# MSP-EXP430F5529LP.net
KiCad netlist of a schematic drawn in EAGLE
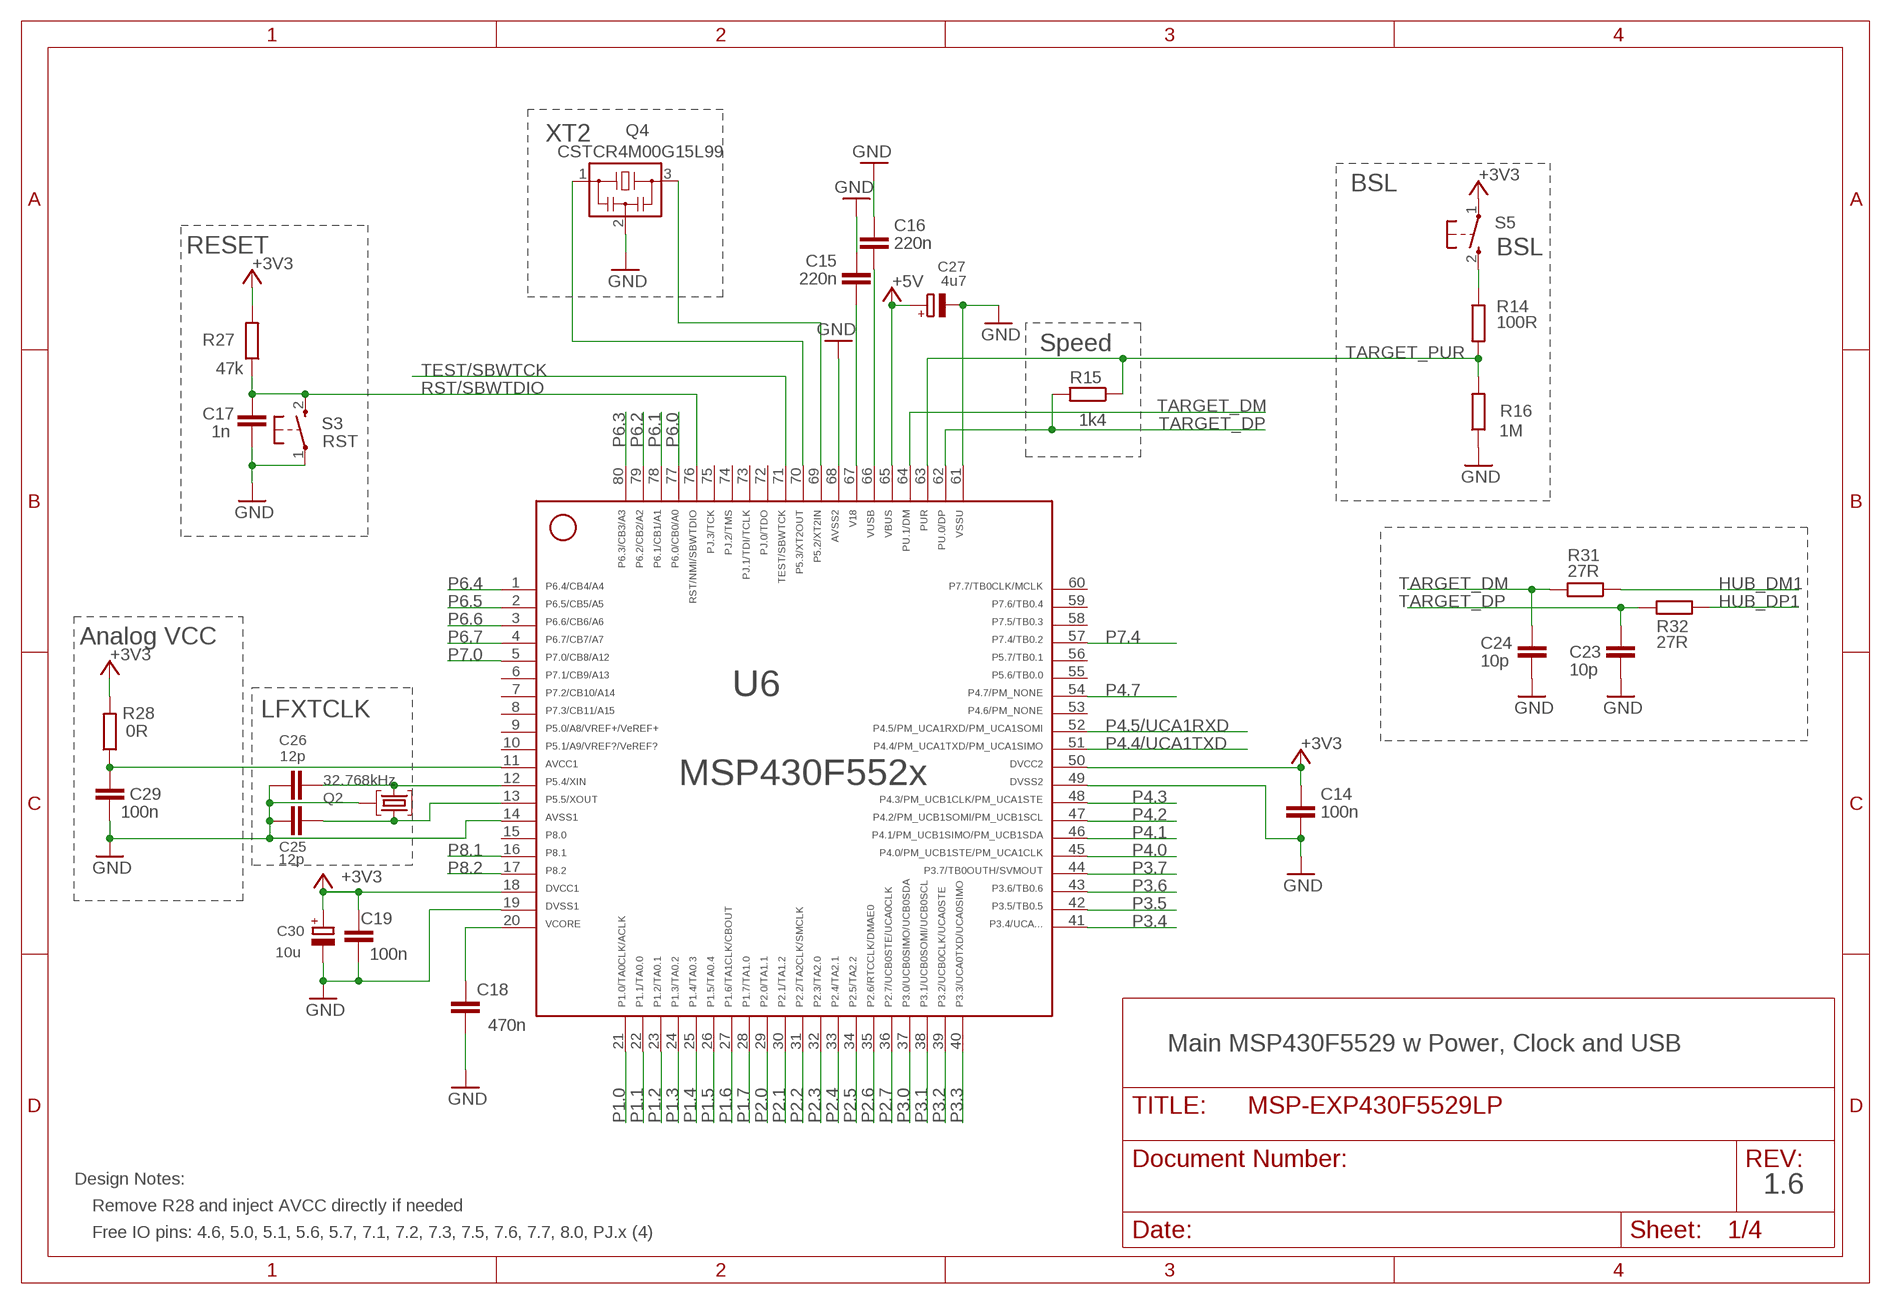
[diagram p0: schematic, sheet 1]
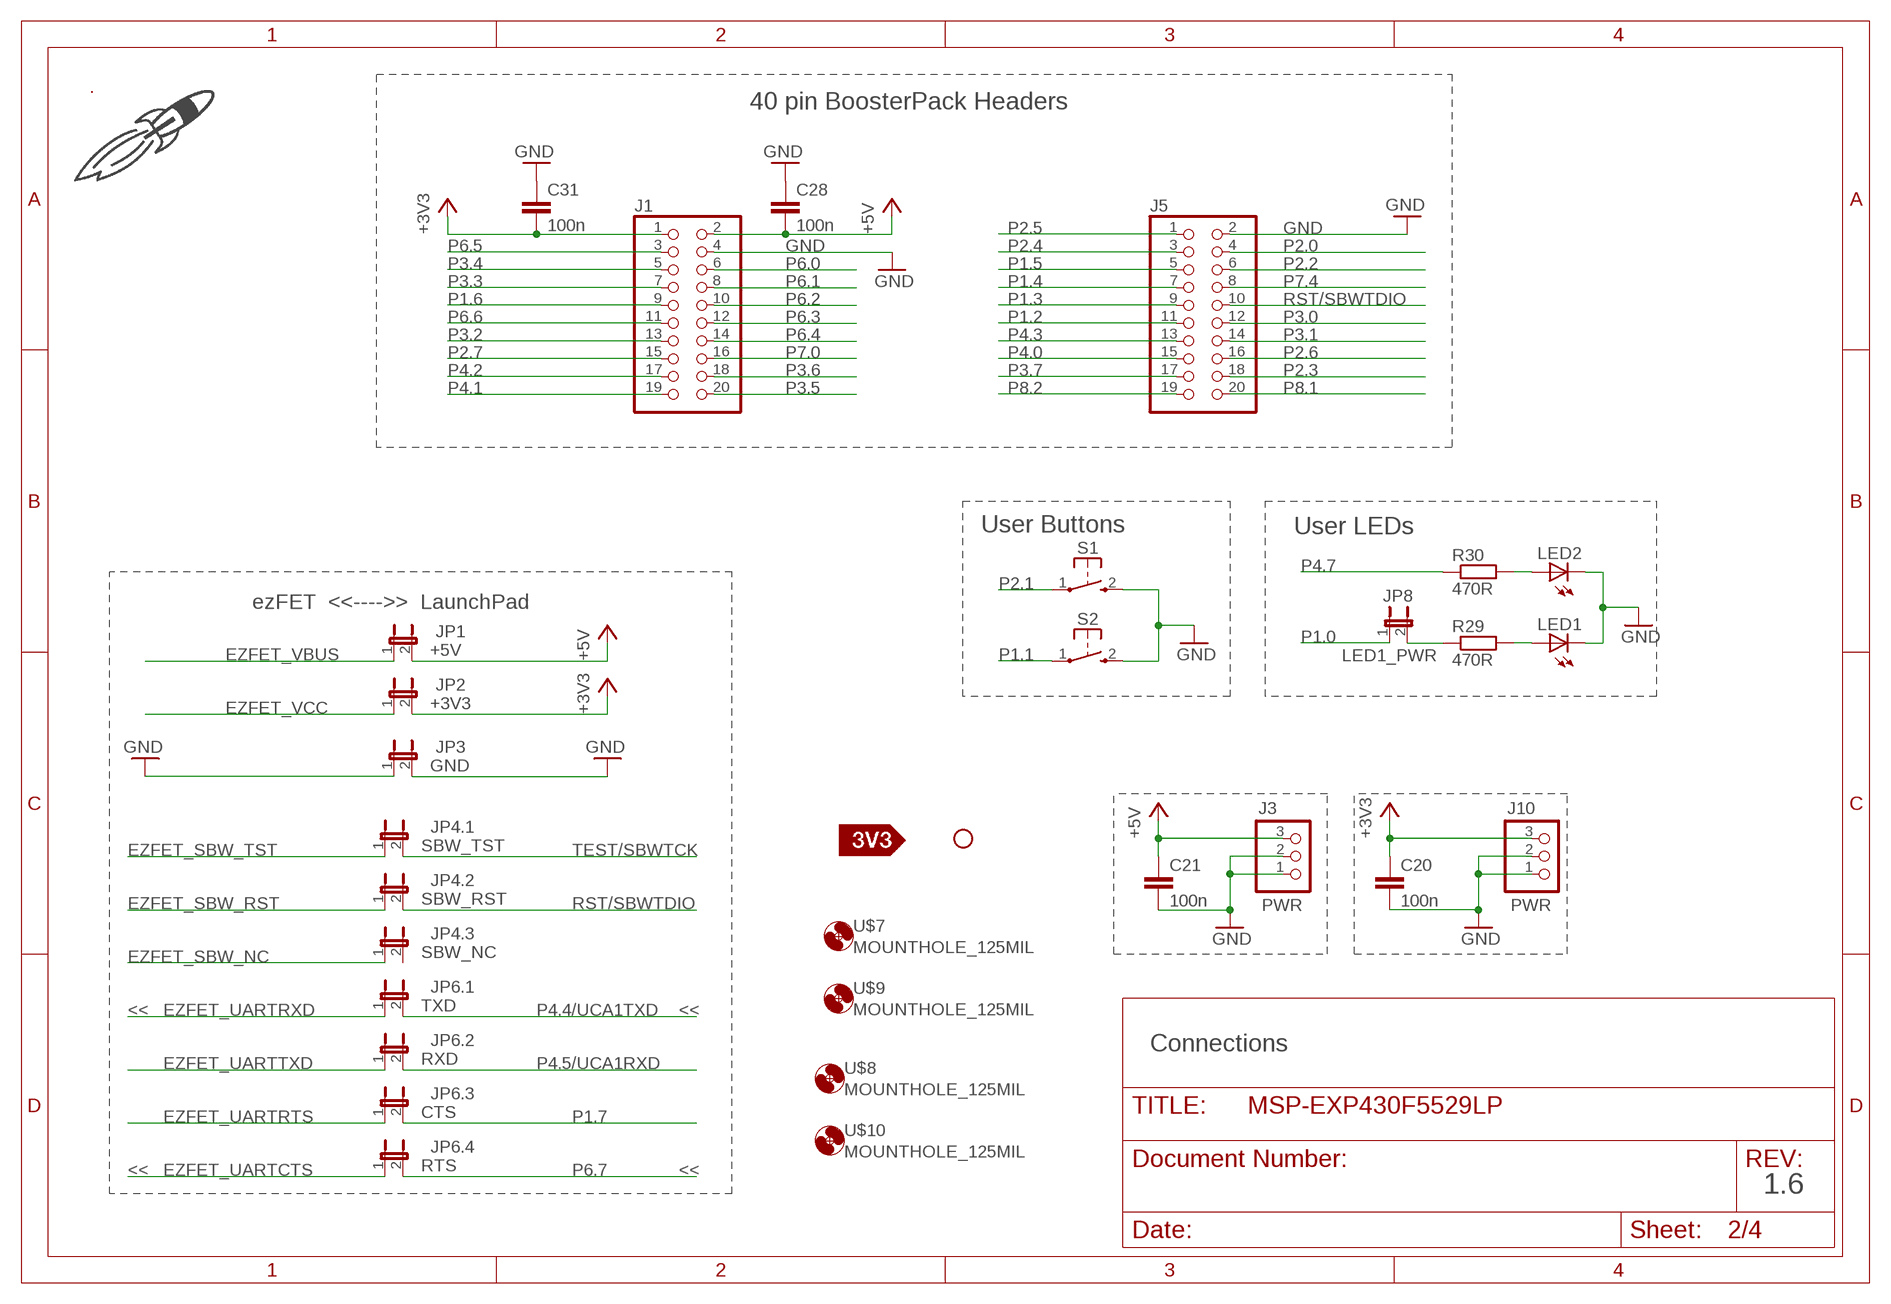
[diagram p1: schematic, sheet 2]
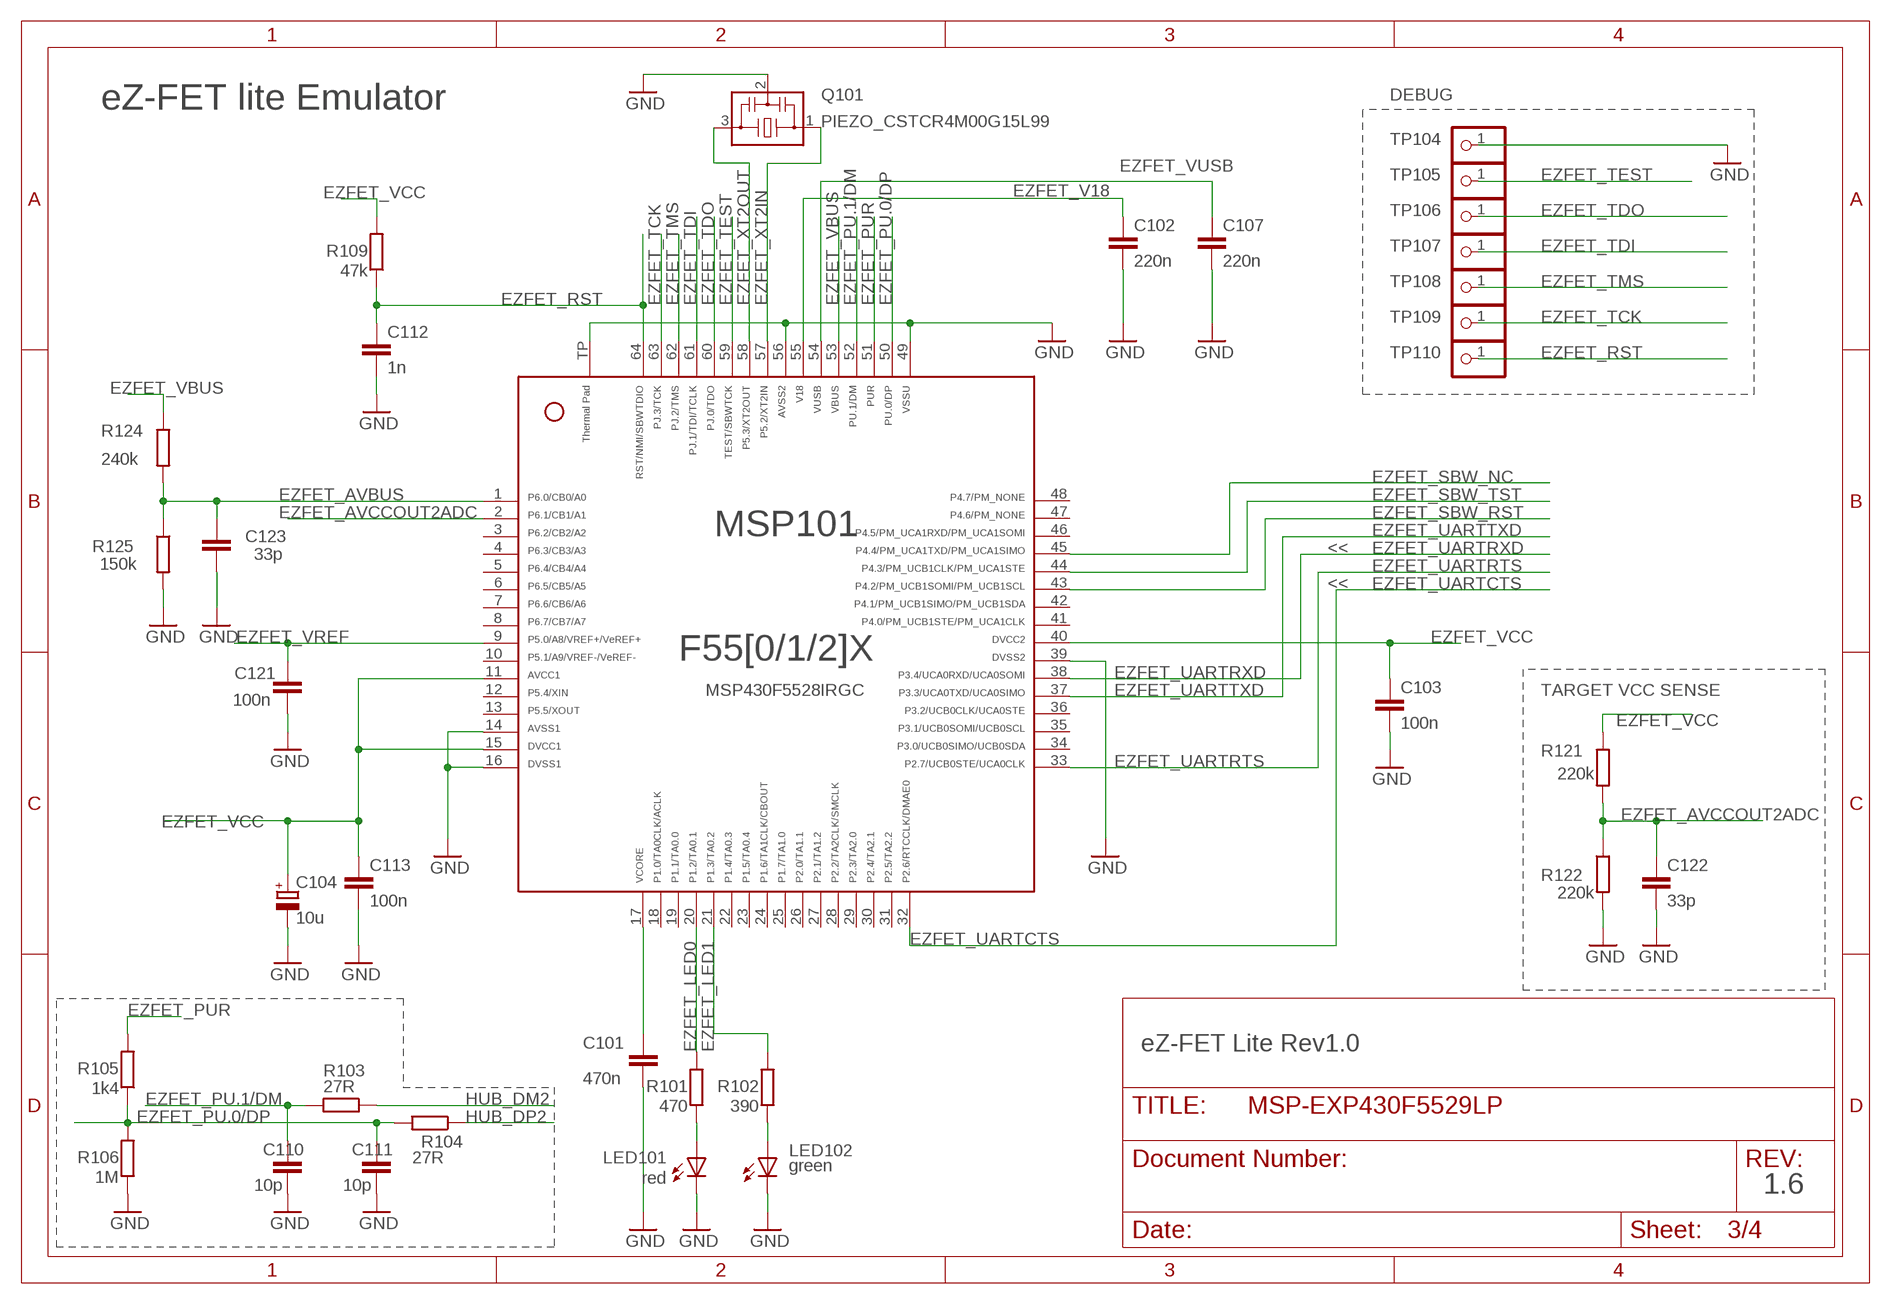
[diagram p2: schematic, sheet 3]
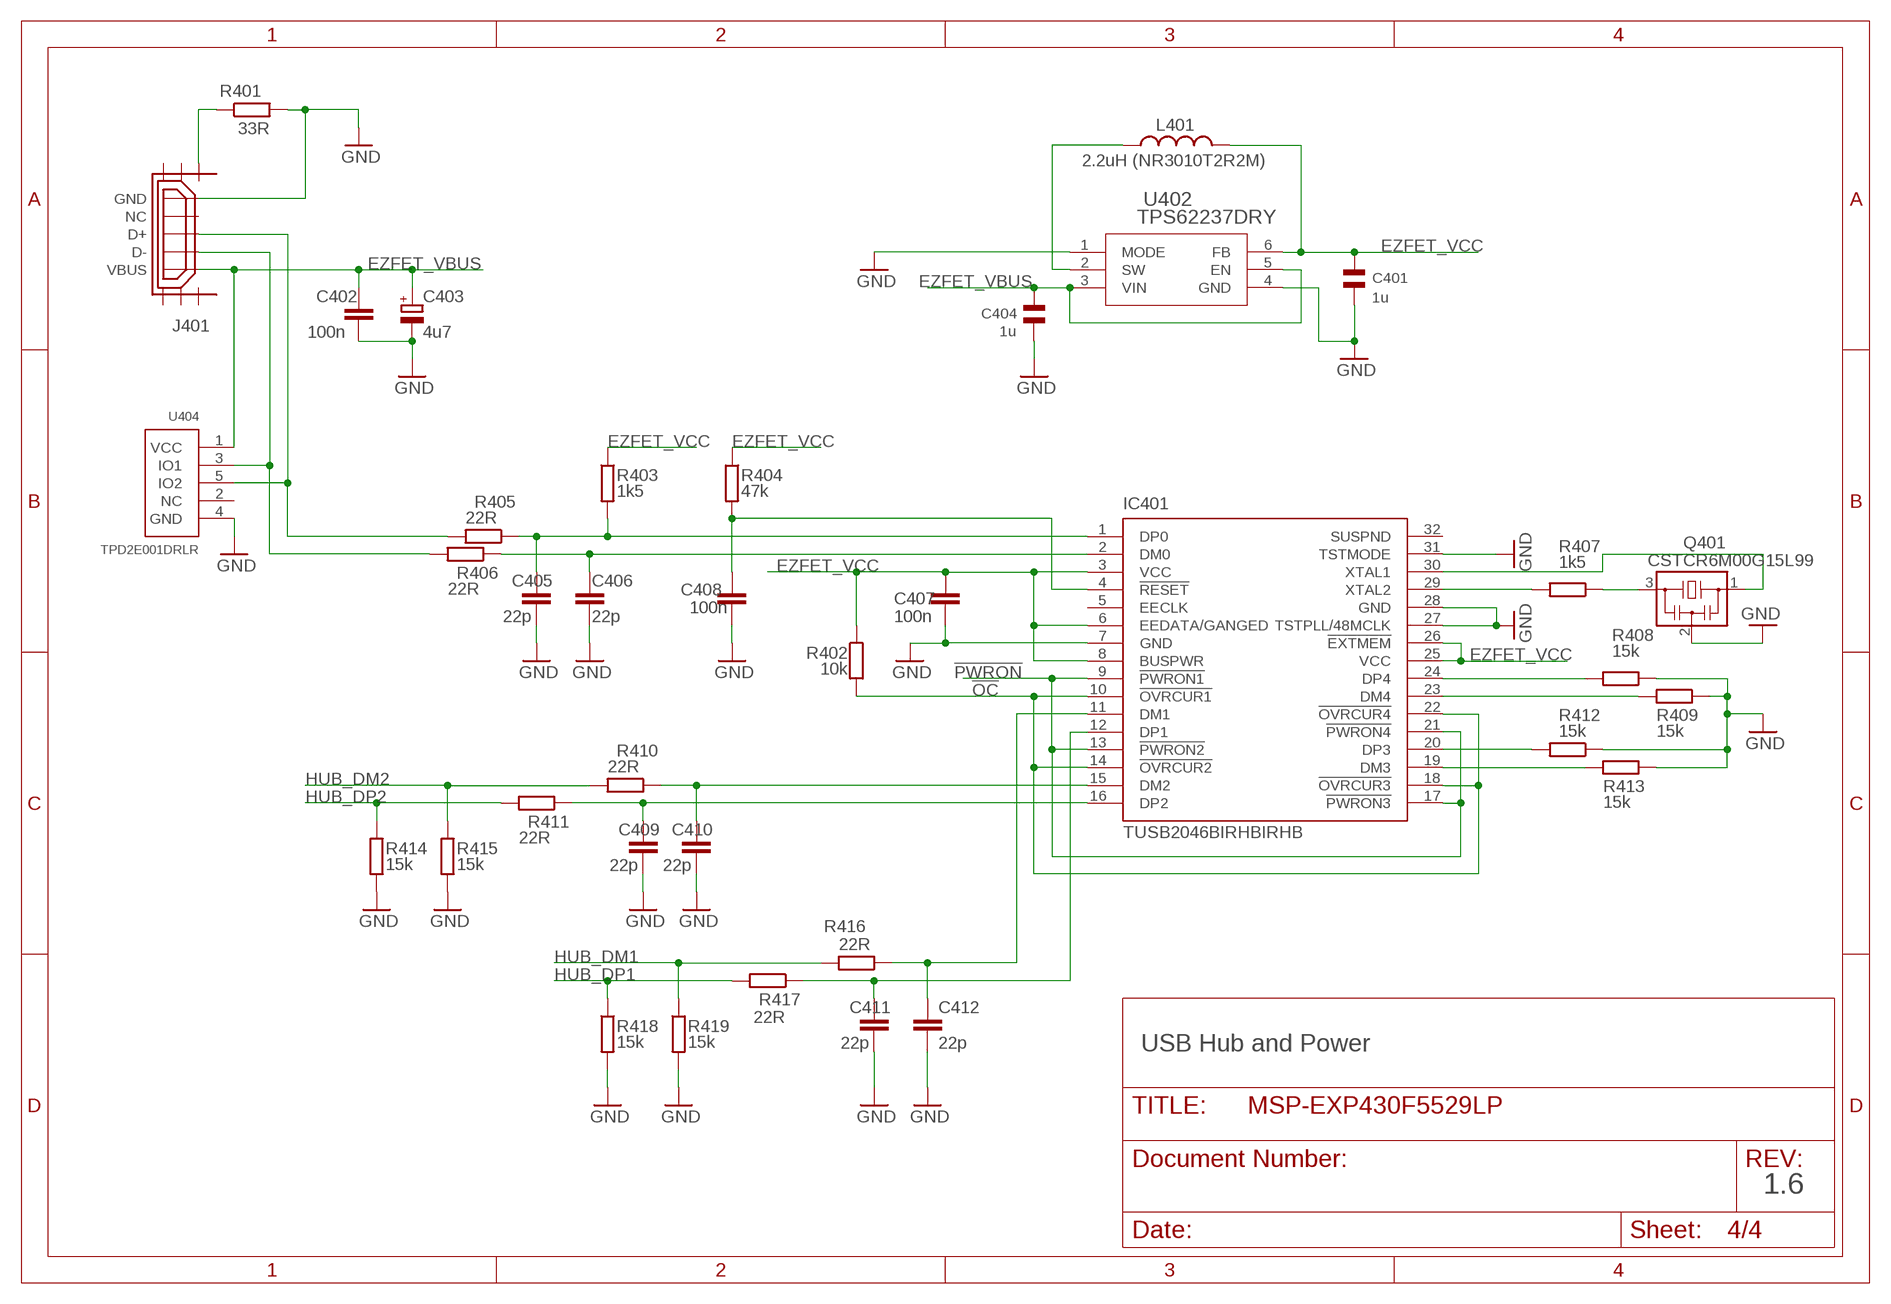
[diagram p3: schematic, sheet 4]

(export (version "E")
  (design (tool "Eeschema 10.0.6"))
  (components
    (comp (ref "C101")
      (value "470n")
      (footprint "eagle-import:0402")
      (libsource (lib "eagle-import") (part "C-EUCM0402"))
    )
    (comp (ref "C102")
      (value "220n")
      (footprint "eagle-import:0402")
      (libsource (lib "eagle-import") (part "C-EUCM0402"))
    )
    (comp (ref "C103")
      (value "100n")
      (footprint "eagle-import:0402")
      (libsource (lib "eagle-import") (part "C-EUCM0402"))
    )
    (comp (ref "C104")
      (value "10u")
      (footprint "eagle-import:A_3216-18R")
      (libsource (lib "eagle-import") (part "CPOL-EUA/3216-18R"))
    )
    (comp (ref "C107")
      (value "220n")
      (footprint "eagle-import:0402")
      (libsource (lib "eagle-import") (part "C-EUCM0402"))
    )
    (comp (ref "C110")
      (value "10p")
      (footprint "eagle-import:0402")
      (libsource (lib "eagle-import") (part "C-EUCM0402"))
    )
    (comp (ref "C111")
      (value "10p")
      (footprint "eagle-import:0402")
      (libsource (lib "eagle-import") (part "C-EUCM0402"))
    )
    (comp (ref "C112")
      (value "1n")
      (footprint "eagle-import:0402")
      (libsource (lib "eagle-import") (part "C-EUCM0402"))
    )
    (comp (ref "C113")
      (value "100n")
      (footprint "eagle-import:0402")
      (libsource (lib "eagle-import") (part "C-EUCM0402"))
    )
    (comp (ref "C121")
      (value "100n")
      (footprint "eagle-import:0402")
      (libsource (lib "eagle-import") (part "C-EUCM0402"))
    )
    (comp (ref "C122")
      (value "33p")
      (footprint "eagle-import:0402")
      (libsource (lib "eagle-import") (part "C-EUCM0402"))
    )
    (comp (ref "C123")
      (value "33p")
      (footprint "eagle-import:0402")
      (libsource (lib "eagle-import") (part "C-EUCM0402"))
    )
    (comp (ref "LED101")
      (value "red")
      (footprint "eagle-import:CHIP-LED0603")
      (libsource (lib "eagle-import") (part "LEDCHIP-LED0603"))
    )
    (comp (ref "LED102")
      (value "green")
      (footprint "eagle-import:CHIP-LED0603")
      (libsource (lib "eagle-import") (part "LEDCHIP-LED0603"))
    )
    (comp (ref "MSP101")
      (value "MSP430F5528IRGC")
      (footprint "eagle-import:RGC64")
      (libsource (lib "eagle-import") (part "F55[0/1/2]X---RGC64"))
    )
    (comp (ref "Q101")
      (value "PIEZO_CSTCR4M00G15L99")
      (footprint "eagle-import:MURATA-FILTER_CSTCR")
      (fields (field (name "MPN") "CSTCR6M00G53-R0"))
      (libsource (lib "eagle-import") (part "MURATA-FILTER_CSTCR6M00G53Z"))
    )
    (comp (ref "R101")
      (value "470")
      (footprint "eagle-import:0402")
      (libsource (lib "eagle-import") (part "R-EU_RM0402"))
    )
    (comp (ref "R102")
      (value "390")
      (footprint "eagle-import:0402")
      (libsource (lib "eagle-import") (part "R-EU_RM0402"))
    )
    (comp (ref "R103")
      (value "27R")
      (footprint "eagle-import:0402")
      (libsource (lib "eagle-import") (part "R-EU_RM0402"))
    )
    (comp (ref "R104")
      (value "27R")
      (footprint "eagle-import:0402")
      (libsource (lib "eagle-import") (part "R-EU_RM0402"))
    )
    (comp (ref "R105")
      (value "1k4")
      (footprint "eagle-import:0402")
      (libsource (lib "eagle-import") (part "R-EU_RM0402"))
    )
    (comp (ref "R106")
      (value "1M")
      (footprint "eagle-import:0402")
      (libsource (lib "eagle-import") (part "R-EU_RM0402"))
    )
    (comp (ref "R109")
      (value "47k")
      (footprint "eagle-import:0402")
      (libsource (lib "eagle-import") (part "R-EU_RM0402"))
    )
    (comp (ref "R121")
      (value "220k")
      (footprint "eagle-import:0402")
      (libsource (lib "eagle-import") (part "R-EU_RM0402"))
    )
    (comp (ref "R122")
      (value "220k")
      (footprint "eagle-import:0402")
      (libsource (lib "eagle-import") (part "R-EU_RM0402"))
    )
    (comp (ref "R124")
      (value "240k")
      (footprint "eagle-import:0402")
      (libsource (lib "eagle-import") (part "R-EU_RM0402"))
    )
    (comp (ref "R125")
      (value "150k")
      (footprint "eagle-import:0402")
      (libsource (lib "eagle-import") (part "R-EU_RM0402"))
    )
    (comp (ref "TP104")
      (value "TEST_PIN2")
      (footprint "eagle-import:1X01")
      (libsource (lib "eagle-import") (part "PINHD-1X1"))
    )
    (comp (ref "TP105")
      (value "TEST_PIN2")
      (footprint "eagle-import:1X01")
      (libsource (lib "eagle-import") (part "PINHD-1X1"))
    )
    (comp (ref "TP106")
      (value "TEST_PIN2")
      (footprint "eagle-import:1X01")
      (libsource (lib "eagle-import") (part "PINHD-1X1"))
    )
    (comp (ref "TP107")
      (value "TEST_PIN2")
      (footprint "eagle-import:1X01")
      (libsource (lib "eagle-import") (part "PINHD-1X1"))
    )
    (comp (ref "TP108")
      (value "TEST_PIN2")
      (footprint "eagle-import:1X01")
      (libsource (lib "eagle-import") (part "PINHD-1X1"))
    )
    (comp (ref "TP109")
      (value "TEST_PIN2")
      (footprint "eagle-import:1X01")
      (libsource (lib "eagle-import") (part "PINHD-1X1"))
    )
    (comp (ref "TP110")
      (value "TEST_PIN2")
      (footprint "eagle-import:1X01")
      (libsource (lib "eagle-import") (part "PINHD-1X1"))
    )
    (comp (ref "C20")
      (value "100n")
      (footprint "eagle-import:0402")
      (libsource (lib "eagle-import") (part "C-EUCM0402"))
    )
    (comp (ref "C21")
      (value "100n")
      (footprint "eagle-import:0402")
      (libsource (lib "eagle-import") (part "C-EUCM0402"))
    )
    (comp (ref "C28")
      (value "100n")
      (footprint "eagle-import:0402")
      (libsource (lib "eagle-import") (part "C-EUCM0402"))
    )
    (comp (ref "C31")
      (value "100n")
      (footprint "eagle-import:0402")
      (libsource (lib "eagle-import") (part "C-EUCM0402"))
    )
    (comp (ref "DRAW1")
      (value "LOGO-ROCKET-20X13MM-SCH-S")
      (footprint "eagle-import:LOGO-ROCKET-10X7MM-BRD")
      (libsource (lib "eagle-import") (part "LOGO-ROCKET-20X13MM-SCH-S"))
    )
    (comp (ref "J1")
      (value "PINHD-2X10")
      (footprint "eagle-import:2X10")
      (libsource (lib "eagle-import") (part "PINHD-2X10"))
    )
    (comp (ref "J3")
      (value "PWR")
      (footprint "eagle-import:1X03")
      (libsource (lib "eagle-import") (part "PINHD-1X3"))
    )
    (comp (ref "J5")
      (value "PINHD-2X10")
      (footprint "eagle-import:2X10")
      (libsource (lib "eagle-import") (part "PINHD-2X10"))
    )
    (comp (ref "J10")
      (value "PWR")
      (footprint "eagle-import:1X03")
      (libsource (lib "eagle-import") (part "PINHD-1X3"))
    )
    (comp (ref "JP1")
      (value "+5V")
      (footprint "eagle-import:JP1M")
      (libsource (lib "eagle-import") (part "JP1M"))
    )
    (comp (ref "JP2")
      (value "+3V3")
      (footprint "eagle-import:JP1M")
      (libsource (lib "eagle-import") (part "JP1M"))
    )
    (comp (ref "JP3")
      (value "GND")
      (footprint "eagle-import:JP1M")
      (libsource (lib "eagle-import") (part "JP1M"))
    )
    (comp (ref "JP4.1")
      (value "SBW_TST")
      (footprint "eagle-import:JP1M")
      (libsource (lib "eagle-import") (part "JP1M"))
    )
    (comp (ref "JP4.2")
      (value "SBW_RST")
      (footprint "eagle-import:JP1M")
      (libsource (lib "eagle-import") (part "JP1M"))
    )
    (comp (ref "JP4.3")
      (value "SBW_NC")
      (footprint "eagle-import:JP1M")
      (libsource (lib "eagle-import") (part "JP1M"))
    )
    (comp (ref "JP6.1")
      (value "TXD")
      (footprint "eagle-import:JP1M")
      (libsource (lib "eagle-import") (part "JP1M"))
    )
    (comp (ref "JP6.2")
      (value "RXD")
      (footprint "eagle-import:JP1M")
      (libsource (lib "eagle-import") (part "JP1M"))
    )
    (comp (ref "JP6.3")
      (value "CTS")
      (footprint "eagle-import:JP1M")
      (libsource (lib "eagle-import") (part "JP1M"))
    )
    (comp (ref "JP6.4")
      (value "RTS")
      (footprint "eagle-import:JP1M")
      (libsource (lib "eagle-import") (part "JP1M"))
    )
    (comp (ref "JP8")
      (value "LED1_PWR")
      (footprint "eagle-import:JP1")
      (libsource (lib "eagle-import") (part "JP1E"))
    )
    (comp (ref "LED1")
      (value "LEDCHIPLED_0603")
      (footprint "eagle-import:CHIPLED_0603")
      (libsource (lib "eagle-import") (part "LEDCHIPLED_0603"))
    )
    (comp (ref "LED2")
      (value "LEDCHIPLED_0603")
      (footprint "eagle-import:CHIPLED_0603")
      (libsource (lib "eagle-import") (part "LEDCHIPLED_0603"))
    )
    (comp (ref "R29")
      (value "470R")
      (footprint "eagle-import:0402")
      (libsource (lib "eagle-import") (part "R-EU_RM0402"))
    )
    (comp (ref "R30")
      (value "470R")
      (footprint "eagle-import:0402")
      (libsource (lib "eagle-import") (part "R-EU_RM0402"))
    )
    (comp (ref "S1")
      (value "PB")
      (footprint "eagle-import:PBTH")
      (libsource (lib "eagle-import") (part "PB"))
    )
    (comp (ref "S2")
      (value "PB")
      (footprint "eagle-import:PBTH")
      (libsource (lib "eagle-import") (part "PB"))
    )
    (comp (ref "U$4")
      (value "MS_TM")
      (footprint "eagle-import:MS_TM")
      (libsource (lib "eagle-import") (part "MS_TM"))
    )
    (comp (ref "U$6")
      (value "SILK_3V3_TAG")
      (footprint "eagle-import:SILK_3V3_TAG")
      (libsource (lib "eagle-import") (part "SILK_3V3_TAG"))
    )
    (comp (ref "U$7")
      (value "MOUNTHOLE_125MIL")
      (footprint "eagle-import:MOUNTHOLE_125MIL")
      (libsource (lib "eagle-import") (part "MOUNTHOLE_125MIL"))
    )
    (comp (ref "U$8")
      (value "MOUNTHOLE_125MIL")
      (footprint "eagle-import:MOUNTHOLE_125MIL")
      (libsource (lib "eagle-import") (part "MOUNTHOLE_125MIL"))
    )
    (comp (ref "U$9")
      (value "MOUNTHOLE_125MIL")
      (footprint "eagle-import:MOUNTHOLE_125MIL")
      (libsource (lib "eagle-import") (part "MOUNTHOLE_125MIL"))
    )
    (comp (ref "U$10")
      (value "MOUNTHOLE_125MIL")
      (footprint "eagle-import:MOUNTHOLE_125MIL")
      (libsource (lib "eagle-import") (part "MOUNTHOLE_125MIL"))
    )
    (comp (ref "U$11")
      (value "5529LP_REARSILK_REV1_6")
      (footprint "eagle-import:5529LP_REARSILK_REV1_6")
      (libsource (lib "eagle-import") (part "5529LP_REARSILK_REV1_6"))
    )
    (comp (ref "C14")
      (value "100n")
      (footprint "eagle-import:0402")
      (libsource (lib "eagle-import") (part "C-EUCM0402"))
    )
    (comp (ref "C15")
      (value "220n")
      (footprint "eagle-import:0402")
      (libsource (lib "eagle-import") (part "C-EUCM0402"))
    )
    (comp (ref "C16")
      (value "220n")
      (footprint "eagle-import:0402")
      (libsource (lib "eagle-import") (part "C-EUCM0402"))
    )
    (comp (ref "C17")
      (value "1n")
      (footprint "eagle-import:0402")
      (libsource (lib "eagle-import") (part "C-EUCM0402"))
    )
    (comp (ref "C18")
      (value "470n")
      (footprint "eagle-import:0402")
      (libsource (lib "eagle-import") (part "C-EUCM0402"))
    )
    (comp (ref "C19")
      (value "100n")
      (footprint "eagle-import:0402")
      (libsource (lib "eagle-import") (part "C-EUCM0402"))
    )
    (comp (ref "C23")
      (value "10p")
      (footprint "eagle-import:0402")
      (libsource (lib "eagle-import") (part "C-EUCM0402"))
    )
    (comp (ref "C24")
      (value "10p")
      (footprint "eagle-import:0402")
      (libsource (lib "eagle-import") (part "C-EUCM0402"))
    )
    (comp (ref "C25")
      (value "12p")
      (footprint "eagle-import:0402")
      (libsource (lib "eagle-import") (part "C-EUCM0402"))
    )
    (comp (ref "C26")
      (value "12p")
      (footprint "eagle-import:0402")
      (libsource (lib "eagle-import") (part "C-EUCM0402"))
    )
    (comp (ref "C27")
      (value "4u7")
      (footprint "eagle-import:A_3216-18R")
      (libsource (lib "eagle-import") (part "CPOL-EUA/3216-18R"))
    )
    (comp (ref "C29")
      (value "100n")
      (footprint "eagle-import:0402")
      (libsource (lib "eagle-import") (part "C-EUCM0402"))
    )
    (comp (ref "C30")
      (value "10u")
      (footprint "eagle-import:A_3216-18R")
      (libsource (lib "eagle-import") (part "CPOL-EUA/3216-18R"))
    )
    (comp (ref "Q2")
      (value "32.768kHz")
      (footprint "eagle-import:MS3V-T1R")
      (libsource (lib "eagle-import") (part "MS3V-T1R"))
    )
    (comp (ref "Q4")
      (value "CSTCR4M00G15L99")
      (footprint "eagle-import:MURATA-FILTER_CSTCR")
      (fields (field (name "MPN") "CSTCR6M00G53-R0"))
      (libsource (lib "eagle-import") (part "MURATA-FILTER_CSTCR6M00G53Z"))
    )
    (comp (ref "R14")
      (value "100R")
      (footprint "eagle-import:0402")
      (libsource (lib "eagle-import") (part "R-EU_RM0402"))
    )
    (comp (ref "R15")
      (value "1k4")
      (footprint "eagle-import:0402")
      (libsource (lib "eagle-import") (part "R-EU_RM0402"))
    )
    (comp (ref "R16")
      (value "1M")
      (footprint "eagle-import:0402")
      (libsource (lib "eagle-import") (part "R-EU_RM0402"))
    )
    (comp (ref "R27")
      (value "47k")
      (footprint "eagle-import:0402")
      (libsource (lib "eagle-import") (part "R-EU_RM0402"))
    )
    (comp (ref "R28")
      (value "0R")
      (footprint "eagle-import:0402")
      (libsource (lib "eagle-import") (part "R-EU_RM0402"))
    )
    (comp (ref "R31")
      (value "27R")
      (footprint "eagle-import:0402")
      (libsource (lib "eagle-import") (part "R-EU_RM0402"))
    )
    (comp (ref "R32")
      (value "27R")
      (footprint "eagle-import:0402")
      (libsource (lib "eagle-import") (part "R-EU_RM0402"))
    )
    (comp (ref "S3")
      (value "RST")
      (footprint "eagle-import:PBTH")
      (libsource (lib "eagle-import") (part "PB"))
    )
    (comp (ref "S5")
      (value "BSL")
      (footprint "eagle-import:PBTH")
      (libsource (lib "eagle-import") (part "PB"))
    )
    (comp (ref "U6")
      (value "MSP430F5529IPNR")
      (footprint "eagle-import:PN80")
      (libsource (lib "eagle-import") (part "F552X---PN80"))
    )
    (comp (ref "C401")
      (value "1u")
      (footprint "eagle-import:CSMD0805")
      (libsource (lib "eagle-import") (part "CSMD0805"))
    )
    (comp (ref "C402")
      (value "100n")
      (footprint "eagle-import:0402")
      (libsource (lib "eagle-import") (part "C-EUCM0402"))
    )
    (comp (ref "C403")
      (value "4u7")
      (footprint "eagle-import:A_3216-18R")
      (libsource (lib "eagle-import") (part "CPOL-EUA/3216-18R"))
    )
    (comp (ref "C404")
      (value "1u")
      (footprint "eagle-import:CSMD0805")
      (libsource (lib "eagle-import") (part "CSMD0805"))
    )
    (comp (ref "C405")
      (value "22p")
      (footprint "eagle-import:0402")
      (libsource (lib "eagle-import") (part "C-EUCM0402"))
    )
    (comp (ref "C406")
      (value "22p")
      (footprint "eagle-import:0402")
      (libsource (lib "eagle-import") (part "C-EUCM0402"))
    )
    (comp (ref "C407")
      (value "100n")
      (footprint "eagle-import:0402")
      (libsource (lib "eagle-import") (part "C-EUCM0402"))
    )
    (comp (ref "C408")
      (value "100n")
      (footprint "eagle-import:0402")
      (libsource (lib "eagle-import") (part "C-EUCM0402"))
    )
    (comp (ref "C409")
      (value "22p")
      (footprint "eagle-import:0402")
      (libsource (lib "eagle-import") (part "C-EUCM0402"))
    )
    (comp (ref "C410")
      (value "22p")
      (footprint "eagle-import:0402")
      (libsource (lib "eagle-import") (part "C-EUCM0402"))
    )
    (comp (ref "C411")
      (value "22p")
      (footprint "eagle-import:0402")
      (libsource (lib "eagle-import") (part "C-EUCM0402"))
    )
    (comp (ref "C412")
      (value "22p")
      (footprint "eagle-import:0402")
      (libsource (lib "eagle-import") (part "C-EUCM0402"))
    )
    (comp (ref "IC401")
      (value "TUSB2046BIRHBIRHB")
      (footprint "eagle-import:RHB_S-PQFP-N32")
      (fields (field (name "MPN") "TUSB2046BIRHBT"))
      (libsource (lib "eagle-import") (part "TUSB2046BIRHBIRHB"))
    )
    (comp (ref "J401")
      (value "USB_MICRO_FLIPPED")
      (footprint "eagle-import:HIROSE-ZX62R-B-5P")
      (libsource (lib "eagle-import") (part "USB_MICRO_FLIPPED"))
    )
    (comp (ref "L401")
      (value "2.2uH (NR3010T2R2M)")
      (footprint "eagle-import:L-NR3010")
      (libsource (lib "eagle-import") (part "L-NR3010"))
    )
    (comp (ref "Q401")
      (value "CSTCR6M00G15L99")
      (footprint "eagle-import:MURATA-FILTER_CSTCR")
      (fields (field (name "MPN") "CSTCR6M00G53-R0"))
      (libsource (lib "eagle-import") (part "MURATA-FILTER_CSTCR6M00G53Z"))
    )
    (comp (ref "R401")
      (value "33R")
      (footprint "eagle-import:0402")
      (libsource (lib "eagle-import") (part "R-EU_RM0402"))
    )
    (comp (ref "R402")
      (value "10k")
      (footprint "eagle-import:0402")
      (libsource (lib "eagle-import") (part "R-EU_RM0402"))
    )
    (comp (ref "R403")
      (value "1k5")
      (footprint "eagle-import:0402")
      (libsource (lib "eagle-import") (part "R-EU_RM0402"))
    )
    (comp (ref "R404")
      (value "47k")
      (footprint "eagle-import:0402")
      (libsource (lib "eagle-import") (part "R-EU_RM0402"))
    )
    (comp (ref "R405")
      (value "22R")
      (footprint "eagle-import:0402")
      (libsource (lib "eagle-import") (part "R-EU_RM0402"))
    )
    (comp (ref "R406")
      (value "22R")
      (footprint "eagle-import:0402")
      (libsource (lib "eagle-import") (part "R-EU_RM0402"))
    )
    (comp (ref "R407")
      (value "1k5")
      (footprint "eagle-import:0402")
      (libsource (lib "eagle-import") (part "R-EU_RM0402"))
    )
    (comp (ref "R408")
      (value "15k")
      (footprint "eagle-import:0402")
      (libsource (lib "eagle-import") (part "R-EU_RM0402"))
    )
    (comp (ref "R409")
      (value "15k")
      (footprint "eagle-import:0402")
      (libsource (lib "eagle-import") (part "R-EU_RM0402"))
    )
    (comp (ref "R410")
      (value "22R")
      (footprint "eagle-import:0402")
      (libsource (lib "eagle-import") (part "R-EU_RM0402"))
    )
    (comp (ref "R411")
      (value "22R")
      (footprint "eagle-import:0402")
      (libsource (lib "eagle-import") (part "R-EU_RM0402"))
    )
    (comp (ref "R412")
      (value "15k")
      (footprint "eagle-import:0402")
      (libsource (lib "eagle-import") (part "R-EU_RM0402"))
    )
    (comp (ref "R413")
      (value "15k")
      (footprint "eagle-import:0402")
      (libsource (lib "eagle-import") (part "R-EU_RM0402"))
    )
    (comp (ref "R414")
      (value "15k")
      (footprint "eagle-import:0402")
      (libsource (lib "eagle-import") (part "R-EU_RM0402"))
    )
    (comp (ref "R415")
      (value "15k")
      (footprint "eagle-import:0402")
      (libsource (lib "eagle-import") (part "R-EU_RM0402"))
    )
    (comp (ref "R416")
      (value "22R")
      (footprint "eagle-import:0402")
      (libsource (lib "eagle-import") (part "R-EU_RM0402"))
    )
    (comp (ref "R417")
      (value "22R")
      (footprint "eagle-import:0402")
      (libsource (lib "eagle-import") (part "R-EU_RM0402"))
    )
    (comp (ref "R418")
      (value "15k")
      (footprint "eagle-import:0402")
      (libsource (lib "eagle-import") (part "R-EU_RM0402"))
    )
    (comp (ref "R419")
      (value "15k")
      (footprint "eagle-import:0402")
      (libsource (lib "eagle-import") (part "R-EU_RM0402"))
    )
    (comp (ref "U402")
      (value "TPS62237DRY")
      (footprint "eagle-import:DRY6")
      (fields
        (field (name "GENERIC_PART_NUMBER") "TPS62231")
        (field (name "MANUFACTURER") "Texas Instruments")
        (field (name "MANUFACTURER_PART_NUMBER") "tps62231_dry_6")
      )
      (libsource (lib "eagle-import") (part "TPS6223X_DRY_6"))
    )
    (comp (ref "U404")
      (value "TPD2E001DRLR")
      (footprint "eagle-import:TPD2E001-DRL")
      (libsource (lib "eagle-import") (part "TPD2E001"))
    )
  )
  (nets
    (net (code "1") (name "+3V3") (class "Default")
      (node (ref "C14") (pin "1") (pinfunction "1_1") (pintype "passive"))
      (node (ref "C19") (pin "2") (pinfunction "2_2") (pintype "passive"))
      (node (ref "C20") (pin "1") (pinfunction "1_1") (pintype "passive"))
      (node (ref "C30") (pin "+") (pinfunction "+_+") (pintype "passive"))
      (node (ref "C31") (pin "2") (pinfunction "2_2") (pintype "passive"))
      (node (ref "J1") (pin "1") (pinfunction "1_1") (pintype "passive"))
      (node (ref "J10") (pin "3") (pinfunction "3_3") (pintype "passive"))
      (node (ref "JP2") (pin "2") (pinfunction "2_2") (pintype "passive"))
      (node (ref "R27") (pin "2") (pinfunction "2_2") (pintype "passive"))
      (node (ref "R28") (pin "2") (pinfunction "2_2") (pintype "passive"))
      (node (ref "S5") (pin "1") (pinfunction "P_1") (pintype "passive"))
      (node (ref "U6") (pin "18") (pinfunction "18_18") (pintype "power_in"))
      (node (ref "U6") (pin "50") (pinfunction "50_50") (pintype "power_in"))
    )
    (net (code "2") (name "+5V") (class "Default")
      (node (ref "C21") (pin "1") (pinfunction "1_1") (pintype "passive"))
      (node (ref "C27") (pin "+") (pinfunction "+_+") (pintype "passive"))
      (node (ref "C28") (pin "2") (pinfunction "2_2") (pintype "passive"))
      (node (ref "J1") (pin "2") (pinfunction "2_2") (pintype "passive"))
      (node (ref "J3") (pin "3") (pinfunction "3_3") (pintype "passive"))
      (node (ref "JP1") (pin "2") (pinfunction "2_2") (pintype "passive"))
      (node (ref "U6") (pin "65") (pinfunction "65_65") (pintype "power_in"))
    )
    (net (code "3") (name "EZFET_AVBUS") (class "Default")
      (node (ref "C123") (pin "2") (pinfunction "2_2") (pintype "passive"))
      (node (ref "MSP101") (pin "1") (pinfunction "1_1") (pintype "bidirectional"))
      (node (ref "R124") (pin "2") (pinfunction "2_2") (pintype "passive"))
      (node (ref "R125") (pin "1") (pinfunction "1_1") (pintype "passive"))
    )
    (net (code "4") (name "EZFET_AVCCOUT2ADC") (class "Default")
      (node (ref "C122") (pin "2") (pinfunction "2_2") (pintype "passive"))
      (node (ref "MSP101") (pin "2") (pinfunction "2_2") (pintype "bidirectional"))
      (node (ref "R121") (pin "2") (pinfunction "2_2") (pintype "passive"))
      (node (ref "R122") (pin "1") (pinfunction "1_1") (pintype "passive"))
    )
    (net (code "5") (name "EZFET_LED0") (class "Default")
      (node (ref "MSP101") (pin "20") (pinfunction "20_20") (pintype "bidirectional"))
      (node (ref "R101") (pin "2") (pinfunction "2_2") (pintype "passive"))
    )
    (net (code "6") (name "EZFET_LED1") (class "Default")
      (node (ref "MSP101") (pin "21") (pinfunction "21_21") (pintype "bidirectional"))
      (node (ref "R102") (pin "2") (pinfunction "2_2") (pintype "passive"))
    )
    (net (code "7") (name "EZFET_PU.0{slash}DP") (class "Default")
      (node (ref "C111") (pin "1") (pinfunction "1_1") (pintype "passive"))
      (node (ref "MSP101") (pin "50") (pinfunction "50_50") (pintype "bidirectional"))
      (node (ref "R104") (pin "2") (pinfunction "2_2") (pintype "passive"))
      (node (ref "R105") (pin "1") (pinfunction "1_1") (pintype "passive"))
      (node (ref "R106") (pin "2") (pinfunction "2_2") (pintype "passive"))
    )
    (net (code "8") (name "EZFET_PU.1{slash}DM") (class "Default")
      (node (ref "C110") (pin "1") (pinfunction "1_1") (pintype "passive"))
      (node (ref "MSP101") (pin "52") (pinfunction "52_52") (pintype "bidirectional"))
      (node (ref "R103") (pin "2") (pinfunction "2_2") (pintype "passive"))
    )
    (net (code "9") (name "EZFET_PUR") (class "Default")
      (node (ref "MSP101") (pin "51") (pinfunction "51_51") (pintype "bidirectional"))
      (node (ref "R105") (pin "2") (pinfunction "2_2") (pintype "passive"))
    )
    (net (code "10") (name "EZFET_RST") (class "Default")
      (node (ref "C112") (pin "1") (pinfunction "1_1") (pintype "passive"))
      (node (ref "MSP101") (pin "64") (pinfunction "64_64") (pintype "bidirectional"))
      (node (ref "R109") (pin "1") (pinfunction "1_1") (pintype "passive"))
      (node (ref "TP110") (pin "1") (pinfunction "1_1") (pintype "passive"))
    )
    (net (code "11") (name "EZFET_SBW_NC") (class "Default")
      (node (ref "JP4.3") (pin "1") (pinfunction "1_1") (pintype "passive"))
      (node (ref "MSP101") (pin "45") (pinfunction "45_45") (pintype "bidirectional"))
    )
    (net (code "12") (name "EZFET_SBW_RST") (class "Default")
      (node (ref "JP4.2") (pin "1") (pinfunction "1_1") (pintype "passive"))
      (node (ref "MSP101") (pin "43") (pinfunction "43_43") (pintype "bidirectional"))
    )
    (net (code "13") (name "EZFET_SBW_TST") (class "Default")
      (node (ref "JP4.1") (pin "1") (pinfunction "1_1") (pintype "passive"))
      (node (ref "MSP101") (pin "44") (pinfunction "44_44") (pintype "bidirectional"))
    )
    (net (code "14") (name "EZFET_TCK") (class "Default")
      (node (ref "MSP101") (pin "63") (pinfunction "63_63") (pintype "bidirectional"))
      (node (ref "TP109") (pin "1") (pinfunction "1_1") (pintype "passive"))
    )
    (net (code "15") (name "EZFET_TDI") (class "Default")
      (node (ref "MSP101") (pin "61") (pinfunction "61_61") (pintype "bidirectional"))
      (node (ref "TP107") (pin "1") (pinfunction "1_1") (pintype "passive"))
    )
    (net (code "16") (name "EZFET_TDO") (class "Default")
      (node (ref "MSP101") (pin "60") (pinfunction "60_60") (pintype "bidirectional"))
      (node (ref "TP106") (pin "1") (pinfunction "1_1") (pintype "passive"))
    )
    (net (code "17") (name "EZFET_TEST") (class "Default")
      (node (ref "MSP101") (pin "59") (pinfunction "59_59") (pintype "input"))
      (node (ref "TP105") (pin "1") (pinfunction "1_1") (pintype "passive"))
    )
    (net (code "18") (name "EZFET_TMS") (class "Default")
      (node (ref "MSP101") (pin "62") (pinfunction "62_62") (pintype "bidirectional"))
      (node (ref "TP108") (pin "1") (pinfunction "1_1") (pintype "passive"))
    )
    (net (code "19") (name "EZFET_UARTCTS") (class "Default")
      (node (ref "JP6.4") (pin "1") (pinfunction "1_1") (pintype "passive"))
      (node (ref "MSP101") (pin "32") (pinfunction "32_32") (pintype "bidirectional"))
    )
    (net (code "20") (name "EZFET_UARTRTS") (class "Default")
      (node (ref "JP6.3") (pin "1") (pinfunction "1_1") (pintype "passive"))
      (node (ref "MSP101") (pin "33") (pinfunction "33_33") (pintype "bidirectional"))
    )
    (net (code "21") (name "EZFET_UARTRXD") (class "Default")
      (node (ref "JP6.1") (pin "1") (pinfunction "1_1") (pintype "passive"))
      (node (ref "MSP101") (pin "38") (pinfunction "38_38") (pintype "bidirectional"))
    )
    (net (code "22") (name "EZFET_UARTTXD") (class "Default")
      (node (ref "JP6.2") (pin "1") (pinfunction "1_1") (pintype "passive"))
      (node (ref "MSP101") (pin "37") (pinfunction "37_37") (pintype "bidirectional"))
    )
    (net (code "23") (name "EZFET_V18") (class "Default")
      (node (ref "C102") (pin "1") (pinfunction "1_1") (pintype "passive"))
      (node (ref "MSP101") (pin "55") (pinfunction "55_55") (pintype "power_in"))
    )
    (net (code "24") (name "EZFET_VBUS") (class "Default")
      (node (ref "C402") (pin "1") (pinfunction "1_1") (pintype "passive"))
      (node (ref "C403") (pin "+") (pinfunction "+_+") (pintype "passive"))
      (node (ref "C404") (pin "2") (pinfunction "2_2") (pintype "passive"))
      (node (ref "J401") (pin "VBUS") (pinfunction "VBUS_VBUS") (pintype "input"))
      (node (ref "JP1") (pin "1") (pinfunction "1_1") (pintype "passive"))
      (node (ref "MSP101") (pin "53") (pinfunction "53_53") (pintype "power_in"))
      (node (ref "R124") (pin "1") (pinfunction "1_1") (pintype "passive"))
      (node (ref "U402") (pin "3") (pinfunction "VIN_3") (pintype "power_in"))
      (node (ref "U402") (pin "5") (pinfunction "EN_5") (pintype "input"))
      (node (ref "U404") (pin "1") (pinfunction "VCC_1") (pintype "power_in"))
    )
    (net (code "25") (name "EZFET_VCC") (class "Default")
      (node (ref "C103") (pin "1") (pinfunction "1_1") (pintype "passive"))
      (node (ref "C104") (pin "+") (pinfunction "+_+") (pintype "passive"))
      (node (ref "C113") (pin "1") (pinfunction "1_1") (pintype "passive"))
      (node (ref "C401") (pin "2") (pinfunction "2_2") (pintype "passive"))
      (node (ref "C407") (pin "1") (pinfunction "1_1") (pintype "passive"))
      (node (ref "IC401") (pin "25") (pinfunction "VCC_25") (pintype "power_in"))
      (node (ref "IC401") (pin "26") (pinfunction "~{EXTMEM}_26") (pintype "input"))
      (node (ref "IC401") (pin "3") (pinfunction "VCC_3") (pintype "power_in"))
      (node (ref "IC401") (pin "6") (pinfunction "EEDATA/GANGED_6") (pintype "bidirectional"))
      (node (ref "IC401") (pin "8") (pinfunction "BUSPWR_8") (pintype "input"))
      (node (ref "JP2") (pin "1") (pinfunction "1_1") (pintype "passive"))
      (node (ref "L401") (pin "P$2") (pinfunction "2_P$2") (pintype "passive"))
      (node (ref "MSP101") (pin "11") (pinfunction "11_11") (pintype "power_in"))
      (node (ref "MSP101") (pin "15") (pinfunction "15_15") (pintype "power_in"))
      (node (ref "MSP101") (pin "40") (pinfunction "40_40") (pintype "power_in"))
      (node (ref "R109") (pin "2") (pinfunction "2_2") (pintype "passive"))
      (node (ref "R121") (pin "1") (pinfunction "1_1") (pintype "passive"))
      (node (ref "R402") (pin "1") (pinfunction "1_1") (pintype "passive"))
      (node (ref "R403") (pin "1") (pinfunction "1_1") (pintype "passive"))
      (node (ref "R404") (pin "1") (pinfunction "1_1") (pintype "passive"))
      (node (ref "U402") (pin "6") (pinfunction "FB_6") (pintype "input"))
    )
    (net (code "26") (name "EZFET_VREF") (class "Default")
      (node (ref "C121") (pin "1") (pinfunction "1_1") (pintype "passive"))
      (node (ref "MSP101") (pin "9") (pinfunction "9_9") (pintype "bidirectional"))
    )
    (net (code "27") (name "EZFET_VUSB") (class "Default")
      (node (ref "C107") (pin "1") (pinfunction "1_1") (pintype "passive"))
      (node (ref "MSP101") (pin "54") (pinfunction "54_54") (pintype "power_in"))
    )
    (net (code "28") (name "EZFET_XT2IN") (class "Default")
      (node (ref "MSP101") (pin "57") (pinfunction "57_57") (pintype "bidirectional"))
      (node (ref "Q101") (pin "1") (pinfunction "1_1") (pintype "passive"))
    )
    (net (code "29") (name "EZFET_XT2OUT") (class "Default")
      (node (ref "MSP101") (pin "58") (pinfunction "58_58") (pintype "bidirectional"))
      (node (ref "Q101") (pin "3") (pinfunction "3_3") (pintype "passive"))
    )
    (net (code "30") (name "GND") (class "Default")
      (node (ref "C101") (pin "2") (pinfunction "2_2") (pintype "passive"))
      (node (ref "C102") (pin "2") (pinfunction "2_2") (pintype "passive"))
      (node (ref "C103") (pin "2") (pinfunction "2_2") (pintype "passive"))
      (node (ref "C104") (pin "-") (pinfunction "-_-") (pintype "passive"))
      (node (ref "C107") (pin "2") (pinfunction "2_2") (pintype "passive"))
      (node (ref "C110") (pin "2") (pinfunction "2_2") (pintype "passive"))
      (node (ref "C111") (pin "2") (pinfunction "2_2") (pintype "passive"))
      (node (ref "C112") (pin "2") (pinfunction "2_2") (pintype "passive"))
      (node (ref "C113") (pin "2") (pinfunction "2_2") (pintype "passive"))
      (node (ref "C121") (pin "2") (pinfunction "2_2") (pintype "passive"))
      (node (ref "C122") (pin "1") (pinfunction "1_1") (pintype "passive"))
      (node (ref "C123") (pin "1") (pinfunction "1_1") (pintype "passive"))
      (node (ref "C14") (pin "2") (pinfunction "2_2") (pintype "passive"))
      (node (ref "C15") (pin "2") (pinfunction "2_2") (pintype "passive"))
      (node (ref "C16") (pin "2") (pinfunction "2_2") (pintype "passive"))
      (node (ref "C17") (pin "2") (pinfunction "2_2") (pintype "passive"))
      (node (ref "C18") (pin "1") (pinfunction "1_1") (pintype "passive"))
      (node (ref "C19") (pin "1") (pinfunction "1_1") (pintype "passive"))
      (node (ref "C20") (pin "2") (pinfunction "2_2") (pintype "passive"))
      (node (ref "C21") (pin "2") (pinfunction "2_2") (pintype "passive"))
      (node (ref "C23") (pin "2") (pinfunction "2_2") (pintype "passive"))
      (node (ref "C24") (pin "2") (pinfunction "2_2") (pintype "passive"))
      (node (ref "C25") (pin "1") (pinfunction "1_1") (pintype "passive"))
      (node (ref "C26") (pin "1") (pinfunction "1_1") (pintype "passive"))
      (node (ref "C27") (pin "-") (pinfunction "-_-") (pintype "passive"))
      (node (ref "C28") (pin "1") (pinfunction "1_1") (pintype "passive"))
      (node (ref "C29") (pin "2") (pinfunction "2_2") (pintype "passive"))
      (node (ref "C30") (pin "-") (pinfunction "-_-") (pintype "passive"))
      (node (ref "C31") (pin "1") (pinfunction "1_1") (pintype "passive"))
      (node (ref "C401") (pin "1") (pinfunction "1_1") (pintype "passive"))
      (node (ref "C402") (pin "2") (pinfunction "2_2") (pintype "passive"))
      (node (ref "C403") (pin "-") (pinfunction "-_-") (pintype "passive"))
      (node (ref "C404") (pin "1") (pinfunction "1_1") (pintype "passive"))
      (node (ref "C405") (pin "2") (pinfunction "2_2") (pintype "passive"))
      (node (ref "C406") (pin "2") (pinfunction "2_2") (pintype "passive"))
      (node (ref "C407") (pin "2") (pinfunction "2_2") (pintype "passive"))
      (node (ref "C408") (pin "2") (pinfunction "2_2") (pintype "passive"))
      (node (ref "C409") (pin "2") (pinfunction "2_2") (pintype "passive"))
      (node (ref "C410") (pin "2") (pinfunction "2_2") (pintype "passive"))
      (node (ref "C411") (pin "2") (pinfunction "2_2") (pintype "passive"))
      (node (ref "C412") (pin "2") (pinfunction "2_2") (pintype "passive"))
      (node (ref "IC401") (pin "27") (pinfunction "TSTPLL/48MCLK_27") (pintype "bidirectional"))
      (node (ref "IC401") (pin "28") (pinfunction "GND_28") (pintype "power_in"))
      (node (ref "IC401") (pin "31") (pinfunction "TSTMODE_31") (pintype "input"))
      (node (ref "IC401") (pin "7") (pinfunction "GND_7") (pintype "power_in"))
      (node (ref "J1") (pin "4") (pinfunction "4_4") (pintype "passive"))
      (node (ref "J10") (pin "1") (pinfunction "1_1") (pintype "passive"))
      (node (ref "J10") (pin "2") (pinfunction "2_2") (pintype "passive"))
      (node (ref "J3") (pin "1") (pinfunction "1_1") (pintype "passive"))
      (node (ref "J3") (pin "2") (pinfunction "2_2") (pintype "passive"))
      (node (ref "J401") (pin "GND") (pinfunction "GND_GND") (pintype "input"))
      (node (ref "J5") (pin "2") (pinfunction "2_2") (pintype "passive"))
      (node (ref "JP3") (pin "1") (pinfunction "1_1") (pintype "passive"))
      (node (ref "JP3") (pin "2") (pinfunction "2_2") (pintype "passive"))
      (node (ref "LED1") (pin "C") (pinfunction "C_C") (pintype "passive"))
      (node (ref "LED101") (pin "C") (pinfunction "C_C") (pintype "passive"))
      (node (ref "LED102") (pin "C") (pinfunction "C_C") (pintype "passive"))
      (node (ref "LED2") (pin "C") (pinfunction "C_C") (pintype "passive"))
      (node (ref "MSP101") (pin "14") (pinfunction "14_14") (pintype "power_in"))
      (node (ref "MSP101") (pin "16") (pinfunction "16_16") (pintype "power_in"))
      (node (ref "MSP101") (pin "39") (pinfunction "39_39") (pintype "power_in"))
      (node (ref "MSP101") (pin "49") (pinfunction "49_49") (pintype "power_in"))
      (node (ref "MSP101") (pin "56") (pinfunction "56_56") (pintype "power_in"))
      (node (ref "MSP101") (pin "TP") (pinfunction "TP_TP") (pintype "power_in"))
      (node (ref "Q101") (pin "2") (pinfunction "2_2") (pintype "passive"))
      (node (ref "Q2") (pin "P3") (pinfunction "GND_P3") (pintype "power_in"))
      (node (ref "Q4") (pin "2") (pinfunction "2_2") (pintype "passive"))
      (node (ref "Q401") (pin "2") (pinfunction "2_2") (pintype "passive"))
      (node (ref "R106") (pin "1") (pinfunction "1_1") (pintype "passive"))
      (node (ref "R122") (pin "2") (pinfunction "2_2") (pintype "passive"))
      (node (ref "R125") (pin "2") (pinfunction "2_2") (pintype "passive"))
      (node (ref "R16") (pin "1") (pinfunction "1_1") (pintype "passive"))
      (node (ref "R401") (pin "2") (pinfunction "2_2") (pintype "passive"))
      (node (ref "R408") (pin "1") (pinfunction "1_1") (pintype "passive"))
      (node (ref "R409") (pin "1") (pinfunction "1_1") (pintype "passive"))
      (node (ref "R412") (pin "1") (pinfunction "1_1") (pintype "passive"))
      (node (ref "R413") (pin "1") (pinfunction "1_1") (pintype "passive"))
      (node (ref "R414") (pin "2") (pinfunction "2_2") (pintype "passive"))
      (node (ref "R415") (pin "2") (pinfunction "2_2") (pintype "passive"))
      (node (ref "R418") (pin "2") (pinfunction "2_2") (pintype "passive"))
      (node (ref "R419") (pin "2") (pinfunction "2_2") (pintype "passive"))
      (node (ref "S1") (pin "2") (pinfunction "S_2") (pintype "passive"))
      (node (ref "S2") (pin "2") (pinfunction "S_2") (pintype "passive"))
      (node (ref "S3") (pin "1") (pinfunction "P_1") (pintype "passive"))
      (node (ref "TP104") (pin "1") (pinfunction "1_1") (pintype "passive"))
      (node (ref "U402") (pin "1") (pinfunction "MODE_1") (pintype "input"))
      (node (ref "U402") (pin "4") (pinfunction "GND_4") (pintype "power_in"))
      (node (ref "U404") (pin "4") (pinfunction "GND_4") (pintype "power_in"))
      (node (ref "U6") (pin "14") (pinfunction "14_14") (pintype "power_in"))
      (node (ref "U6") (pin "19") (pinfunction "19_19") (pintype "power_in"))
      (node (ref "U6") (pin "49") (pinfunction "49_49") (pintype "power_in"))
      (node (ref "U6") (pin "61") (pinfunction "61_61") (pintype "power_in"))
      (node (ref "U6") (pin "68") (pinfunction "68_68") (pintype "power_in"))
    )
    (net (code "31") (name "HUB_DM1") (class "Default")
      (node (ref "R31") (pin "1") (pinfunction "1_1") (pintype "passive"))
      (node (ref "R416") (pin "2") (pinfunction "2_2") (pintype "passive"))
      (node (ref "R419") (pin "1") (pinfunction "1_1") (pintype "passive"))
    )
    (net (code "32") (name "HUB_DM2") (class "Default")
      (node (ref "R103") (pin "1") (pinfunction "1_1") (pintype "passive"))
      (node (ref "R410") (pin "2") (pinfunction "2_2") (pintype "passive"))
      (node (ref "R415") (pin "1") (pinfunction "1_1") (pintype "passive"))
    )
    (net (code "33") (name "HUB_DP1") (class "Default")
      (node (ref "R32") (pin "1") (pinfunction "1_1") (pintype "passive"))
      (node (ref "R417") (pin "2") (pinfunction "2_2") (pintype "passive"))
      (node (ref "R418") (pin "1") (pinfunction "1_1") (pintype "passive"))
    )
    (net (code "34") (name "HUB_DP2") (class "Default")
      (node (ref "R104") (pin "1") (pinfunction "1_1") (pintype "passive"))
      (node (ref "R411") (pin "2") (pinfunction "2_2") (pintype "passive"))
      (node (ref "R414") (pin "1") (pinfunction "1_1") (pintype "passive"))
    )
    (net (code "35") (name "Net-(C15-Pad1)") (class "Default")
      (node (ref "C15") (pin "1") (pinfunction "1_1") (pintype "passive"))
      (node (ref "U6") (pin "67") (pinfunction "67_67") (pintype "power_in"))
    )
    (net (code "36") (name "Net-(C16-Pad1)") (class "Default")
      (node (ref "C16") (pin "1") (pinfunction "1_1") (pintype "passive"))
      (node (ref "U6") (pin "66") (pinfunction "66_66") (pintype "power_in"))
    )
    (net (code "37") (name "Net-(C18-Pad2)") (class "Default")
      (node (ref "C18") (pin "2") (pinfunction "2_2") (pintype "passive"))
      (node (ref "U6") (pin "20") (pinfunction "20_20") (pintype "power_in"))
    )
    (net (code "38") (name "Net-(C29-Pad1)") (class "Default")
      (node (ref "C29") (pin "1") (pinfunction "1_1") (pintype "passive"))
      (node (ref "R28") (pin "1") (pinfunction "1_1") (pintype "passive"))
      (node (ref "U6") (pin "11") (pinfunction "11_11") (pintype "power_in"))
    )
    (net (code "39") (name "Net-(C101-Pad1)") (class "Default")
      (node (ref "C101") (pin "1") (pinfunction "1_1") (pintype "passive"))
      (node (ref "MSP101") (pin "17") (pinfunction "17_17") (pintype "power_in"))
    )
    (net (code "40") (name "Net-(IC401-DM0)") (class "Default")
      (node (ref "C406") (pin "1") (pinfunction "1_1") (pintype "passive"))
      (node (ref "IC401") (pin "2") (pinfunction "DM0_2") (pintype "bidirectional"))
      (node (ref "R406") (pin "1") (pinfunction "1_1") (pintype "passive"))
    )
    (net (code "41") (name "Net-(IC401-DM1)") (class "Default")
      (node (ref "C412") (pin "1") (pinfunction "1_1") (pintype "passive"))
      (node (ref "IC401") (pin "11") (pinfunction "DM1_11") (pintype "bidirectional"))
      (node (ref "R416") (pin "1") (pinfunction "1_1") (pintype "passive"))
    )
    (net (code "42") (name "Net-(IC401-DM2)") (class "Default")
      (node (ref "C410") (pin "1") (pinfunction "1_1") (pintype "passive"))
      (node (ref "IC401") (pin "15") (pinfunction "DM2_15") (pintype "bidirectional"))
      (node (ref "R410") (pin "1") (pinfunction "1_1") (pintype "passive"))
    )
    (net (code "43") (name "Net-(IC401-DM3)") (class "Default")
      (node (ref "IC401") (pin "19") (pinfunction "DM3_19") (pintype "bidirectional"))
      (node (ref "R413") (pin "2") (pinfunction "2_2") (pintype "passive"))
    )
    (net (code "44") (name "Net-(IC401-DM4)") (class "Default")
      (node (ref "IC401") (pin "23") (pinfunction "DM4_23") (pintype "bidirectional"))
      (node (ref "R409") (pin "2") (pinfunction "2_2") (pintype "passive"))
    )
    (net (code "45") (name "Net-(IC401-DP0)") (class "Default")
      (node (ref "C405") (pin "1") (pinfunction "1_1") (pintype "passive"))
      (node (ref "IC401") (pin "1") (pinfunction "DP0_1") (pintype "bidirectional"))
      (node (ref "R403") (pin "2") (pinfunction "2_2") (pintype "passive"))
      (node (ref "R405") (pin "1") (pinfunction "1_1") (pintype "passive"))
    )
    (net (code "46") (name "Net-(IC401-DP1)") (class "Default")
      (node (ref "C411") (pin "1") (pinfunction "1_1") (pintype "passive"))
      (node (ref "IC401") (pin "12") (pinfunction "DP1_12") (pintype "bidirectional"))
      (node (ref "R417") (pin "1") (pinfunction "1_1") (pintype "passive"))
    )
    (net (code "47") (name "Net-(IC401-DP2)") (class "Default")
      (node (ref "C409") (pin "1") (pinfunction "1_1") (pintype "passive"))
      (node (ref "IC401") (pin "16") (pinfunction "DP2_16") (pintype "bidirectional"))
      (node (ref "R411") (pin "1") (pinfunction "1_1") (pintype "passive"))
    )
    (net (code "48") (name "Net-(IC401-DP3)") (class "Default")
      (node (ref "IC401") (pin "20") (pinfunction "DP3_20") (pintype "bidirectional"))
      (node (ref "R412") (pin "2") (pinfunction "2_2") (pintype "passive"))
    )
    (net (code "49") (name "Net-(IC401-DP4)") (class "Default")
      (node (ref "IC401") (pin "24") (pinfunction "DP4_24") (pintype "bidirectional"))
      (node (ref "R408") (pin "2") (pinfunction "2_2") (pintype "passive"))
    )
    (net (code "50") (name "Net-(IC401-XTAL1)") (class "Default")
      (node (ref "IC401") (pin "30") (pinfunction "XTAL1_30") (pintype "input"))
      (node (ref "Q401") (pin "1") (pinfunction "1_1") (pintype "passive"))
    )
    (net (code "51") (name "Net-(IC401-XTAL2)") (class "Default")
      (node (ref "IC401") (pin "29") (pinfunction "XTAL2_29") (pintype "output"))
      (node (ref "R407") (pin "2") (pinfunction "2_2") (pintype "passive"))
    )
    (net (code "52") (name "Net-(IC401-~{RESET})") (class "Default")
      (node (ref "C408") (pin "1") (pinfunction "1_1") (pintype "passive"))
      (node (ref "IC401") (pin "4") (pinfunction "~{RESET}_4") (pintype "input"))
      (node (ref "R404") (pin "2") (pinfunction "2_2") (pintype "passive"))
    )
    (net (code "53") (name "Net-(J401-PadSHIELD1)") (class "Default")
      (node (ref "J401") (pin "SHIELD1") (pinfunction "SHIELD1_SHIELD1") (pintype "bidirectional"))
      (node (ref "R401") (pin "1") (pinfunction "1_1") (pintype "passive"))
    )
    (net (code "54") (name "Net-(JP8-Pad2)") (class "Default")
      (node (ref "JP8") (pin "2") (pinfunction "2_2") (pintype "passive"))
      (node (ref "R29") (pin "1") (pinfunction "1_1") (pintype "passive"))
    )
    (net (code "55") (name "Net-(L401-1)") (class "Default")
      (node (ref "L401") (pin "P$1") (pinfunction "1_P$1") (pintype "passive"))
      (node (ref "U402") (pin "2") (pinfunction "SW_2") (pintype "output"))
    )
    (net (code "56") (name "Net-(LED1-PadA)") (class "Default")
      (node (ref "LED1") (pin "A") (pinfunction "A_A") (pintype "passive"))
      (node (ref "R29") (pin "2") (pinfunction "2_2") (pintype "passive"))
    )
    (net (code "57") (name "Net-(LED2-PadA)") (class "Default")
      (node (ref "LED2") (pin "A") (pinfunction "A_A") (pintype "passive"))
      (node (ref "R30") (pin "2") (pinfunction "2_2") (pintype "passive"))
    )
    (net (code "58") (name "Net-(LED101-PadA)") (class "Default")
      (node (ref "LED101") (pin "A") (pinfunction "A_A") (pintype "passive"))
      (node (ref "R101") (pin "1") (pinfunction "1_1") (pintype "passive"))
    )
    (net (code "59") (name "Net-(LED102-PadA)") (class "Default")
      (node (ref "LED102") (pin "A") (pinfunction "A_A") (pintype "passive"))
      (node (ref "R102") (pin "1") (pinfunction "1_1") (pintype "passive"))
    )
    (net (code "60") (name "Net-(Q2-1)") (class "Default")
      (node (ref "C25") (pin "2") (pinfunction "2_2") (pintype "passive"))
      (node (ref "Q2") (pin "P1") (pinfunction "1_P1") (pintype "bidirectional"))
      (node (ref "U6") (pin "13") (pinfunction "13_13") (pintype "bidirectional"))
    )
    (net (code "61") (name "Net-(Q2-2)") (class "Default")
      (node (ref "C26") (pin "2") (pinfunction "2_2") (pintype "passive"))
      (node (ref "Q2") (pin "P2") (pinfunction "2_P2") (pintype "bidirectional"))
      (node (ref "U6") (pin "12") (pinfunction "12_12") (pintype "bidirectional"))
    )
    (net (code "62") (name "Net-(Q4-Pad1)") (class "Default")
      (node (ref "Q4") (pin "1") (pinfunction "1_1") (pintype "passive"))
      (node (ref "U6") (pin "70") (pinfunction "70_70") (pintype "bidirectional"))
    )
    (net (code "63") (name "Net-(Q4-Pad3)") (class "Default")
      (node (ref "Q4") (pin "3") (pinfunction "3_3") (pintype "passive"))
      (node (ref "U6") (pin "69") (pinfunction "69_69") (pintype "bidirectional"))
    )
    (net (code "64") (name "Net-(Q401-Pad3)") (class "Default")
      (node (ref "Q401") (pin "3") (pinfunction "3_3") (pintype "passive"))
      (node (ref "R407") (pin "1") (pinfunction "1_1") (pintype "passive"))
    )
    (net (code "65") (name "Net-(S5-S)") (class "Default")
      (node (ref "R14") (pin "1") (pinfunction "1_1") (pintype "passive"))
      (node (ref "S5") (pin "2") (pinfunction "S_2") (pintype "passive"))
    )
    (net (code "66") (name "Net-(U404-IO1)") (class "Default")
      (node (ref "J401") (pin "D-") (pinfunction "D-_D-") (pintype "input"))
      (node (ref "R406") (pin "2") (pinfunction "2_2") (pintype "passive"))
      (node (ref "U404") (pin "3") (pinfunction "IO1_3") (pintype "bidirectional"))
    )
    (net (code "67") (name "Net-(U404-IO2)") (class "Default")
      (node (ref "J401") (pin "D+") (pinfunction "D+_D+") (pintype "input"))
      (node (ref "R405") (pin "2") (pinfunction "2_2") (pintype "passive"))
      (node (ref "U404") (pin "5") (pinfunction "IO2_5") (pintype "bidirectional"))
    )
    (net (code "68") (name "P1.0") (class "Default")
      (node (ref "JP8") (pin "1") (pinfunction "1_1") (pintype "passive"))
      (node (ref "U6") (pin "21") (pinfunction "21_21") (pintype "bidirectional"))
    )
    (net (code "69") (name "P1.1") (class "Default")
      (node (ref "S2") (pin "1") (pinfunction "P_1") (pintype "passive"))
      (node (ref "U6") (pin "22") (pinfunction "22_22") (pintype "bidirectional"))
    )
    (net (code "70") (name "P1.2") (class "Default")
      (node (ref "J5") (pin "11") (pinfunction "11_11") (pintype "passive"))
      (node (ref "U6") (pin "23") (pinfunction "23_23") (pintype "bidirectional"))
    )
    (net (code "71") (name "P1.3") (class "Default")
      (node (ref "J5") (pin "9") (pinfunction "9_9") (pintype "passive"))
      (node (ref "U6") (pin "24") (pinfunction "24_24") (pintype "bidirectional"))
    )
    (net (code "72") (name "P1.4") (class "Default")
      (node (ref "J5") (pin "7") (pinfunction "7_7") (pintype "passive"))
      (node (ref "U6") (pin "25") (pinfunction "25_25") (pintype "bidirectional"))
    )
    (net (code "73") (name "P1.5") (class "Default")
      (node (ref "J5") (pin "5") (pinfunction "5_5") (pintype "passive"))
      (node (ref "U6") (pin "26") (pinfunction "26_26") (pintype "bidirectional"))
    )
    (net (code "74") (name "P1.6") (class "Default")
      (node (ref "J1") (pin "9") (pinfunction "9_9") (pintype "passive"))
      (node (ref "U6") (pin "27") (pinfunction "27_27") (pintype "bidirectional"))
    )
    (net (code "75") (name "P1.7") (class "Default")
      (node (ref "JP6.3") (pin "2") (pinfunction "2_2") (pintype "passive"))
      (node (ref "U6") (pin "28") (pinfunction "28_28") (pintype "bidirectional"))
    )
    (net (code "76") (name "P2.0") (class "Default")
      (node (ref "J5") (pin "4") (pinfunction "4_4") (pintype "passive"))
      (node (ref "U6") (pin "29") (pinfunction "29_29") (pintype "bidirectional"))
    )
    (net (code "77") (name "P2.1") (class "Default")
      (node (ref "S1") (pin "1") (pinfunction "P_1") (pintype "passive"))
      (node (ref "U6") (pin "30") (pinfunction "30_30") (pintype "bidirectional"))
    )
    (net (code "78") (name "P2.2") (class "Default")
      (node (ref "J5") (pin "6") (pinfunction "6_6") (pintype "passive"))
      (node (ref "U6") (pin "31") (pinfunction "31_31") (pintype "bidirectional"))
    )
    (net (code "79") (name "P2.3") (class "Default")
      (node (ref "J5") (pin "18") (pinfunction "18_18") (pintype "passive"))
      (node (ref "U6") (pin "32") (pinfunction "32_32") (pintype "bidirectional"))
    )
    (net (code "80") (name "P2.4") (class "Default")
      (node (ref "J5") (pin "3") (pinfunction "3_3") (pintype "passive"))
      (node (ref "U6") (pin "33") (pinfunction "33_33") (pintype "bidirectional"))
    )
    (net (code "81") (name "P2.5") (class "Default")
      (node (ref "J5") (pin "1") (pinfunction "1_1") (pintype "passive"))
      (node (ref "U6") (pin "34") (pinfunction "34_34") (pintype "bidirectional"))
    )
    (net (code "82") (name "P2.6") (class "Default")
      (node (ref "J5") (pin "16") (pinfunction "16_16") (pintype "passive"))
      (node (ref "U6") (pin "35") (pinfunction "35_35") (pintype "bidirectional"))
    )
    (net (code "83") (name "P2.7") (class "Default")
      (node (ref "J1") (pin "15") (pinfunction "15_15") (pintype "passive"))
      (node (ref "U6") (pin "36") (pinfunction "36_36") (pintype "bidirectional"))
    )
    (net (code "84") (name "P3.0") (class "Default")
      (node (ref "J5") (pin "12") (pinfunction "12_12") (pintype "passive"))
      (node (ref "U6") (pin "37") (pinfunction "37_37") (pintype "bidirectional"))
    )
    (net (code "85") (name "P3.1") (class "Default")
      (node (ref "J5") (pin "14") (pinfunction "14_14") (pintype "passive"))
      (node (ref "U6") (pin "38") (pinfunction "38_38") (pintype "bidirectional"))
    )
    (net (code "86") (name "P3.2") (class "Default")
      (node (ref "J1") (pin "13") (pinfunction "13_13") (pintype "passive"))
      (node (ref "U6") (pin "39") (pinfunction "39_39") (pintype "bidirectional"))
    )
    (net (code "87") (name "P3.3") (class "Default")
      (node (ref "J1") (pin "7") (pinfunction "7_7") (pintype "passive"))
      (node (ref "U6") (pin "40") (pinfunction "40_40") (pintype "bidirectional"))
    )
    (net (code "88") (name "P3.4") (class "Default")
      (node (ref "J1") (pin "5") (pinfunction "5_5") (pintype "passive"))
      (node (ref "U6") (pin "41") (pinfunction "41_41") (pintype "bidirectional"))
    )
    (net (code "89") (name "P3.5") (class "Default")
      (node (ref "J1") (pin "20") (pinfunction "20_20") (pintype "passive"))
      (node (ref "U6") (pin "42") (pinfunction "42_42") (pintype "bidirectional"))
    )
    (net (code "90") (name "P3.6") (class "Default")
      (node (ref "J1") (pin "18") (pinfunction "18_18") (pintype "passive"))
      (node (ref "U6") (pin "43") (pinfunction "43_43") (pintype "bidirectional"))
    )
    (net (code "91") (name "P3.7") (class "Default")
      (node (ref "J5") (pin "17") (pinfunction "17_17") (pintype "passive"))
      (node (ref "U6") (pin "44") (pinfunction "44_44") (pintype "bidirectional"))
    )
    (net (code "92") (name "P4.0") (class "Default")
      (node (ref "J5") (pin "15") (pinfunction "15_15") (pintype "passive"))
      (node (ref "U6") (pin "45") (pinfunction "45_45") (pintype "bidirectional"))
    )
    (net (code "93") (name "P4.1") (class "Default")
      (node (ref "J1") (pin "19") (pinfunction "19_19") (pintype "passive"))
      (node (ref "U6") (pin "46") (pinfunction "46_46") (pintype "bidirectional"))
    )
    (net (code "94") (name "P4.2") (class "Default")
      (node (ref "J1") (pin "17") (pinfunction "17_17") (pintype "passive"))
      (node (ref "U6") (pin "47") (pinfunction "47_47") (pintype "bidirectional"))
    )
    (net (code "95") (name "P4.3") (class "Default")
      (node (ref "J5") (pin "13") (pinfunction "13_13") (pintype "passive"))
      (node (ref "U6") (pin "48") (pinfunction "48_48") (pintype "bidirectional"))
    )
    (net (code "96") (name "P4.4{slash}UCA1TXD") (class "Default")
      (node (ref "JP6.1") (pin "2") (pinfunction "2_2") (pintype "passive"))
      (node (ref "U6") (pin "51") (pinfunction "51_51") (pintype "bidirectional"))
    )
    (net (code "97") (name "P4.5{slash}UCA1RXD") (class "Default")
      (node (ref "JP6.2") (pin "2") (pinfunction "2_2") (pintype "passive"))
      (node (ref "U6") (pin "52") (pinfunction "52_52") (pintype "bidirectional"))
    )
    (net (code "98") (name "P4.7") (class "Default")
      (node (ref "R30") (pin "1") (pinfunction "1_1") (pintype "passive"))
      (node (ref "U6") (pin "54") (pinfunction "54_54") (pintype "bidirectional"))
    )
    (net (code "99") (name "P6.0") (class "Default")
      (node (ref "J1") (pin "6") (pinfunction "6_6") (pintype "passive"))
      (node (ref "U6") (pin "77") (pinfunction "77_77") (pintype "bidirectional"))
    )
    (net (code "100") (name "P6.1") (class "Default")
      (node (ref "J1") (pin "8") (pinfunction "8_8") (pintype "passive"))
      (node (ref "U6") (pin "78") (pinfunction "78_78") (pintype "bidirectional"))
    )
    (net (code "101") (name "P6.2") (class "Default")
      (node (ref "J1") (pin "10") (pinfunction "10_10") (pintype "passive"))
      (node (ref "U6") (pin "79") (pinfunction "79_79") (pintype "bidirectional"))
    )
    (net (code "102") (name "P6.3") (class "Default")
      (node (ref "J1") (pin "12") (pinfunction "12_12") (pintype "passive"))
      (node (ref "U6") (pin "80") (pinfunction "80_80") (pintype "bidirectional"))
    )
    (net (code "103") (name "P6.4") (class "Default")
      (node (ref "J1") (pin "14") (pinfunction "14_14") (pintype "passive"))
      (node (ref "U6") (pin "1") (pinfunction "1_1") (pintype "bidirectional"))
    )
    (net (code "104") (name "P6.5") (class "Default")
      (node (ref "J1") (pin "3") (pinfunction "3_3") (pintype "passive"))
      (node (ref "U6") (pin "2") (pinfunction "2_2") (pintype "bidirectional"))
    )
    (net (code "105") (name "P6.6") (class "Default")
      (node (ref "J1") (pin "11") (pinfunction "11_11") (pintype "passive"))
      (node (ref "U6") (pin "3") (pinfunction "3_3") (pintype "bidirectional"))
    )
    (net (code "106") (name "P6.7") (class "Default")
      (node (ref "JP6.4") (pin "2") (pinfunction "2_2") (pintype "passive"))
      (node (ref "U6") (pin "4") (pinfunction "4_4") (pintype "bidirectional"))
    )
    (net (code "107") (name "P7.0") (class "Default")
      (node (ref "J1") (pin "16") (pinfunction "16_16") (pintype "passive"))
      (node (ref "U6") (pin "5") (pinfunction "5_5") (pintype "bidirectional"))
    )
    (net (code "108") (name "P7.4") (class "Default")
      (node (ref "J5") (pin "8") (pinfunction "8_8") (pintype "passive"))
      (node (ref "U6") (pin "57") (pinfunction "57_57") (pintype "bidirectional"))
    )
    (net (code "109") (name "P8.1") (class "Default")
      (node (ref "J5") (pin "20") (pinfunction "20_20") (pintype "passive"))
      (node (ref "U6") (pin "16") (pinfunction "16_16") (pintype "bidirectional"))
    )
    (net (code "110") (name "P8.2") (class "Default")
      (node (ref "J5") (pin "19") (pinfunction "19_19") (pintype "passive"))
      (node (ref "U6") (pin "17") (pinfunction "17_17") (pintype "bidirectional"))
    )
    (net (code "111") (name "RST{slash}SBWTDIO") (class "Default")
      (node (ref "C17") (pin "1") (pinfunction "1_1") (pintype "passive"))
      (node (ref "J5") (pin "10") (pinfunction "10_10") (pintype "passive"))
      (node (ref "JP4.2") (pin "2") (pinfunction "2_2") (pintype "passive"))
      (node (ref "R27") (pin "1") (pinfunction "1_1") (pintype "passive"))
      (node (ref "S3") (pin "2") (pinfunction "S_2") (pintype "passive"))
      (node (ref "U6") (pin "76") (pinfunction "76_76") (pintype "bidirectional"))
    )
    (net (code "112") (name "TARGET_DM") (class "Default")
      (node (ref "C24") (pin "1") (pinfunction "1_1") (pintype "passive"))
      (node (ref "R31") (pin "2") (pinfunction "2_2") (pintype "passive"))
      (node (ref "U6") (pin "64") (pinfunction "64_64") (pintype "bidirectional"))
    )
    (net (code "113") (name "TARGET_DP") (class "Default")
      (node (ref "C23") (pin "1") (pinfunction "1_1") (pintype "passive"))
      (node (ref "R15") (pin "2") (pinfunction "2_2") (pintype "passive"))
      (node (ref "R32") (pin "2") (pinfunction "2_2") (pintype "passive"))
      (node (ref "U6") (pin "62") (pinfunction "62_62") (pintype "bidirectional"))
    )
    (net (code "114") (name "TARGET_PUR") (class "Default")
      (node (ref "R14") (pin "2") (pinfunction "2_2") (pintype "passive"))
      (node (ref "R15") (pin "1") (pinfunction "1_1") (pintype "passive"))
      (node (ref "R16") (pin "2") (pinfunction "2_2") (pintype "passive"))
      (node (ref "U6") (pin "63") (pinfunction "63_63") (pintype "bidirectional"))
    )
    (net (code "115") (name "TEST{slash}SBWTCK") (class "Default")
      (node (ref "JP4.1") (pin "2") (pinfunction "2_2") (pintype "passive"))
      (node (ref "U6") (pin "71") (pinfunction "71_71") (pintype "input"))
    )
    (net (code "116") (name "unconnected-(IC401-EECLK-Pad5)") (class "Default")
      (node (ref "IC401") (pin "5") (pinfunction "EECLK_5") (pintype "output"))
    )
    (net (code "117") (name "unconnected-(IC401-SUSPND-Pad32)") (class "Default")
      (node (ref "IC401") (pin "32") (pinfunction "SUSPND_32") (pintype "output"))
    )
    (net (code "118") (name "unconnected-(J401-PadNC)") (class "Default")
      (node (ref "J401") (pin "NC") (pinfunction "NC_NC") (pintype "input"))
    )
    (net (code "119") (name "unconnected-(J401-PadSHIELD2)") (class "Default")
      (node (ref "J401") (pin "SHIELD2") (pinfunction "SHIELD2_SHIELD2") (pintype "bidirectional"))
    )
    (net (code "120") (name "unconnected-(J401-PadSHIELD3)") (class "Default")
      (node (ref "J401") (pin "SHIELD3") (pinfunction "SHIELD3_SHIELD3") (pintype "bidirectional"))
    )
    (net (code "121") (name "unconnected-(J401-PadSHIELD4)") (class "Default")
      (node (ref "J401") (pin "SHIELD4") (pinfunction "SHIELD4_SHIELD4") (pintype "bidirectional"))
    )
    (net (code "122") (name "unconnected-(J401-PadSHIELD5)") (class "Default")
      (node (ref "J401") (pin "SHIELD5") (pinfunction "SHIELD5_SHIELD5") (pintype "bidirectional"))
    )
    (net (code "123") (name "unconnected-(J401-PadSHIELD6)") (class "Default")
      (node (ref "J401") (pin "SHIELD6") (pinfunction "SHIELD6_SHIELD6") (pintype "bidirectional"))
    )
    (net (code "124") (name "unconnected-(JP4.3-Pad2)") (class "Default")
      (node (ref "JP4.3") (pin "2") (pinfunction "2_2") (pintype "passive"))
    )
    (net (code "125") (name "unconnected-(MSP101-Pad3)") (class "Default")
      (node (ref "MSP101") (pin "3") (pinfunction "3_3") (pintype "bidirectional"))
    )
    (net (code "126") (name "unconnected-(MSP101-Pad4)") (class "Default")
      (node (ref "MSP101") (pin "4") (pinfunction "4_4") (pintype "bidirectional"))
    )
    (net (code "127") (name "unconnected-(MSP101-Pad5)") (class "Default")
      (node (ref "MSP101") (pin "5") (pinfunction "5_5") (pintype "bidirectional"))
    )
    (net (code "128") (name "unconnected-(MSP101-Pad6)") (class "Default")
      (node (ref "MSP101") (pin "6") (pinfunction "6_6") (pintype "bidirectional"))
    )
    (net (code "129") (name "unconnected-(MSP101-Pad7)") (class "Default")
      (node (ref "MSP101") (pin "7") (pinfunction "7_7") (pintype "bidirectional"))
    )
    (net (code "130") (name "unconnected-(MSP101-Pad8)") (class "Default")
      (node (ref "MSP101") (pin "8") (pinfunction "8_8") (pintype "bidirectional"))
    )
    (net (code "131") (name "unconnected-(MSP101-Pad10)") (class "Default")
      (node (ref "MSP101") (pin "10") (pinfunction "10_10") (pintype "bidirectional"))
    )
    (net (code "132") (name "unconnected-(MSP101-Pad12)") (class "Default")
      (node (ref "MSP101") (pin "12") (pinfunction "12_12") (pintype "bidirectional"))
    )
    (net (code "133") (name "unconnected-(MSP101-Pad13)") (class "Default")
      (node (ref "MSP101") (pin "13") (pinfunction "13_13") (pintype "bidirectional"))
    )
    (net (code "134") (name "unconnected-(MSP101-Pad18)") (class "Default")
      (node (ref "MSP101") (pin "18") (pinfunction "18_18") (pintype "bidirectional"))
    )
    (net (code "135") (name "unconnected-(MSP101-Pad19)") (class "Default")
      (node (ref "MSP101") (pin "19") (pinfunction "19_19") (pintype "bidirectional"))
    )
    (net (code "136") (name "unconnected-(MSP101-Pad22)") (class "Default")
      (node (ref "MSP101") (pin "22") (pinfunction "22_22") (pintype "bidirectional"))
    )
    (net (code "137") (name "unconnected-(MSP101-Pad23)") (class "Default")
      (node (ref "MSP101") (pin "23") (pinfunction "23_23") (pintype "bidirectional"))
    )
    (net (code "138") (name "unconnected-(MSP101-Pad24)") (class "Default")
      (node (ref "MSP101") (pin "24") (pinfunction "24_24") (pintype "bidirectional"))
    )
    (net (code "139") (name "unconnected-(MSP101-Pad25)") (class "Default")
      (node (ref "MSP101") (pin "25") (pinfunction "25_25") (pintype "bidirectional"))
    )
    (net (code "140") (name "unconnected-(MSP101-Pad26)") (class "Default")
      (node (ref "MSP101") (pin "26") (pinfunction "26_26") (pintype "bidirectional"))
    )
    (net (code "141") (name "unconnected-(MSP101-Pad27)") (class "Default")
      (node (ref "MSP101") (pin "27") (pinfunction "27_27") (pintype "bidirectional"))
    )
    (net (code "142") (name "unconnected-(MSP101-Pad28)") (class "Default")
      (node (ref "MSP101") (pin "28") (pinfunction "28_28") (pintype "bidirectional"))
    )
    (net (code "143") (name "unconnected-(MSP101-Pad29)") (class "Default")
      (node (ref "MSP101") (pin "29") (pinfunction "29_29") (pintype "bidirectional"))
    )
    (net (code "144") (name "unconnected-(MSP101-Pad30)") (class "Default")
      (node (ref "MSP101") (pin "30") (pinfunction "30_30") (pintype "bidirectional"))
    )
    (net (code "145") (name "unconnected-(MSP101-Pad31)") (class "Default")
      (node (ref "MSP101") (pin "31") (pinfunction "31_31") (pintype "bidirectional"))
    )
    (net (code "146") (name "unconnected-(MSP101-Pad34)") (class "Default")
      (node (ref "MSP101") (pin "34") (pinfunction "34_34") (pintype "bidirectional"))
    )
    (net (code "147") (name "unconnected-(MSP101-Pad35)") (class "Default")
      (node (ref "MSP101") (pin "35") (pinfunction "35_35") (pintype "bidirectional"))
    )
    (net (code "148") (name "unconnected-(MSP101-Pad36)") (class "Default")
      (node (ref "MSP101") (pin "36") (pinfunction "36_36") (pintype "bidirectional"))
    )
    (net (code "149") (name "unconnected-(MSP101-Pad41)") (class "Default")
      (node (ref "MSP101") (pin "41") (pinfunction "41_41") (pintype "bidirectional"))
    )
    (net (code "150") (name "unconnected-(MSP101-Pad42)") (class "Default")
      (node (ref "MSP101") (pin "42") (pinfunction "42_42") (pintype "bidirectional"))
    )
    (net (code "151") (name "unconnected-(MSP101-Pad46)") (class "Default")
      (node (ref "MSP101") (pin "46") (pinfunction "46_46") (pintype "bidirectional"))
    )
    (net (code "152") (name "unconnected-(MSP101-Pad47)") (class "Default")
      (node (ref "MSP101") (pin "47") (pinfunction "47_47") (pintype "bidirectional"))
    )
    (net (code "153") (name "unconnected-(MSP101-Pad48)") (class "Default")
      (node (ref "MSP101") (pin "48") (pinfunction "48_48") (pintype "bidirectional"))
    )
    (net (code "154") (name "unconnected-(U6-Pad6)") (class "Default")
      (node (ref "U6") (pin "6") (pinfunction "6_6") (pintype "bidirectional"))
    )
    (net (code "155") (name "unconnected-(U6-Pad7)") (class "Default")
      (node (ref "U6") (pin "7") (pinfunction "7_7") (pintype "bidirectional"))
    )
    (net (code "156") (name "unconnected-(U6-Pad8)") (class "Default")
      (node (ref "U6") (pin "8") (pinfunction "8_8") (pintype "bidirectional"))
    )
    (net (code "157") (name "unconnected-(U6-Pad9)") (class "Default")
      (node (ref "U6") (pin "9") (pinfunction "9_9") (pintype "bidirectional"))
    )
    (net (code "158") (name "unconnected-(U6-Pad10)") (class "Default")
      (node (ref "U6") (pin "10") (pinfunction "10_10") (pintype "bidirectional"))
    )
    (net (code "159") (name "unconnected-(U6-Pad15)") (class "Default")
      (node (ref "U6") (pin "15") (pinfunction "15_15") (pintype "bidirectional"))
    )
    (net (code "160") (name "unconnected-(U6-Pad53)") (class "Default")
      (node (ref "U6") (pin "53") (pinfunction "53_53") (pintype "bidirectional"))
    )
    (net (code "161") (name "unconnected-(U6-Pad55)") (class "Default")
      (node (ref "U6") (pin "55") (pinfunction "55_55") (pintype "bidirectional"))
    )
    (net (code "162") (name "unconnected-(U6-Pad56)") (class "Default")
      (node (ref "U6") (pin "56") (pinfunction "56_56") (pintype "bidirectional"))
    )
    (net (code "163") (name "unconnected-(U6-Pad58)") (class "Default")
      (node (ref "U6") (pin "58") (pinfunction "58_58") (pintype "bidirectional"))
    )
    (net (code "164") (name "unconnected-(U6-Pad59)") (class "Default")
      (node (ref "U6") (pin "59") (pinfunction "59_59") (pintype "bidirectional"))
    )
    (net (code "165") (name "unconnected-(U6-Pad60)") (class "Default")
      (node (ref "U6") (pin "60") (pinfunction "60_60") (pintype "bidirectional"))
    )
    (net (code "166") (name "unconnected-(U6-Pad72)") (class "Default")
      (node (ref "U6") (pin "72") (pinfunction "72_72") (pintype "bidirectional"))
    )
    (net (code "167") (name "unconnected-(U6-Pad73)") (class "Default")
      (node (ref "U6") (pin "73") (pinfunction "73_73") (pintype "bidirectional"))
    )
    (net (code "168") (name "unconnected-(U6-Pad74)") (class "Default")
      (node (ref "U6") (pin "74") (pinfunction "74_74") (pintype "bidirectional"))
    )
    (net (code "169") (name "unconnected-(U6-Pad75)") (class "Default")
      (node (ref "U6") (pin "75") (pinfunction "75_75") (pintype "bidirectional"))
    )
    (net (code "170") (name "unconnected-(U404-NC-Pad2)") (class "Default")
      (node (ref "U404") (pin "2") (pinfunction "NC_2") (pintype "no_connect"))
    )
    (net (code "171") (name "~{OC}") (class "Default")
      (node (ref "IC401") (pin "10") (pinfunction "~{OVRCUR1}_10") (pintype "input"))
      (node (ref "IC401") (pin "14") (pinfunction "~{OVRCUR2}_14") (pintype "input"))
      (node (ref "IC401") (pin "18") (pinfunction "~{OVRCUR3}_18") (pintype "input"))
      (node (ref "IC401") (pin "22") (pinfunction "~{OVRCUR4}_22") (pintype "input"))
      (node (ref "R402") (pin "2") (pinfunction "2_2") (pintype "passive"))
    )
    (net (code "172") (name "~{PWRON}") (class "Default")
      (node (ref "IC401") (pin "13") (pinfunction "~{PWRON2}_13") (pintype "output"))
      (node (ref "IC401") (pin "17") (pinfunction "~{PWRON3}_17") (pintype "output"))
      (node (ref "IC401") (pin "21") (pinfunction "~{PWRON4}_21") (pintype "output"))
      (node (ref "IC401") (pin "9") (pinfunction "~{PWRON1}_9") (pintype "output"))
    )
  )
)
